# SzineszFeny.net
KiCad netlist of a schematic drawn in EAGLE
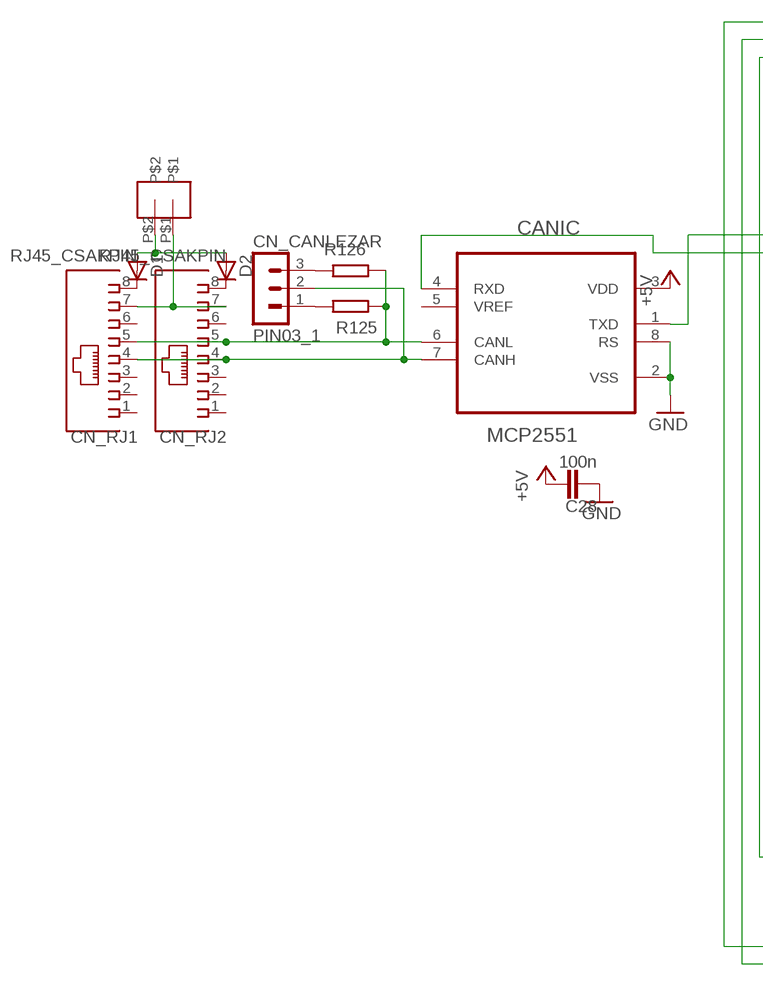
[diagram p0: schematic, sheet 1, part 1 of 2]
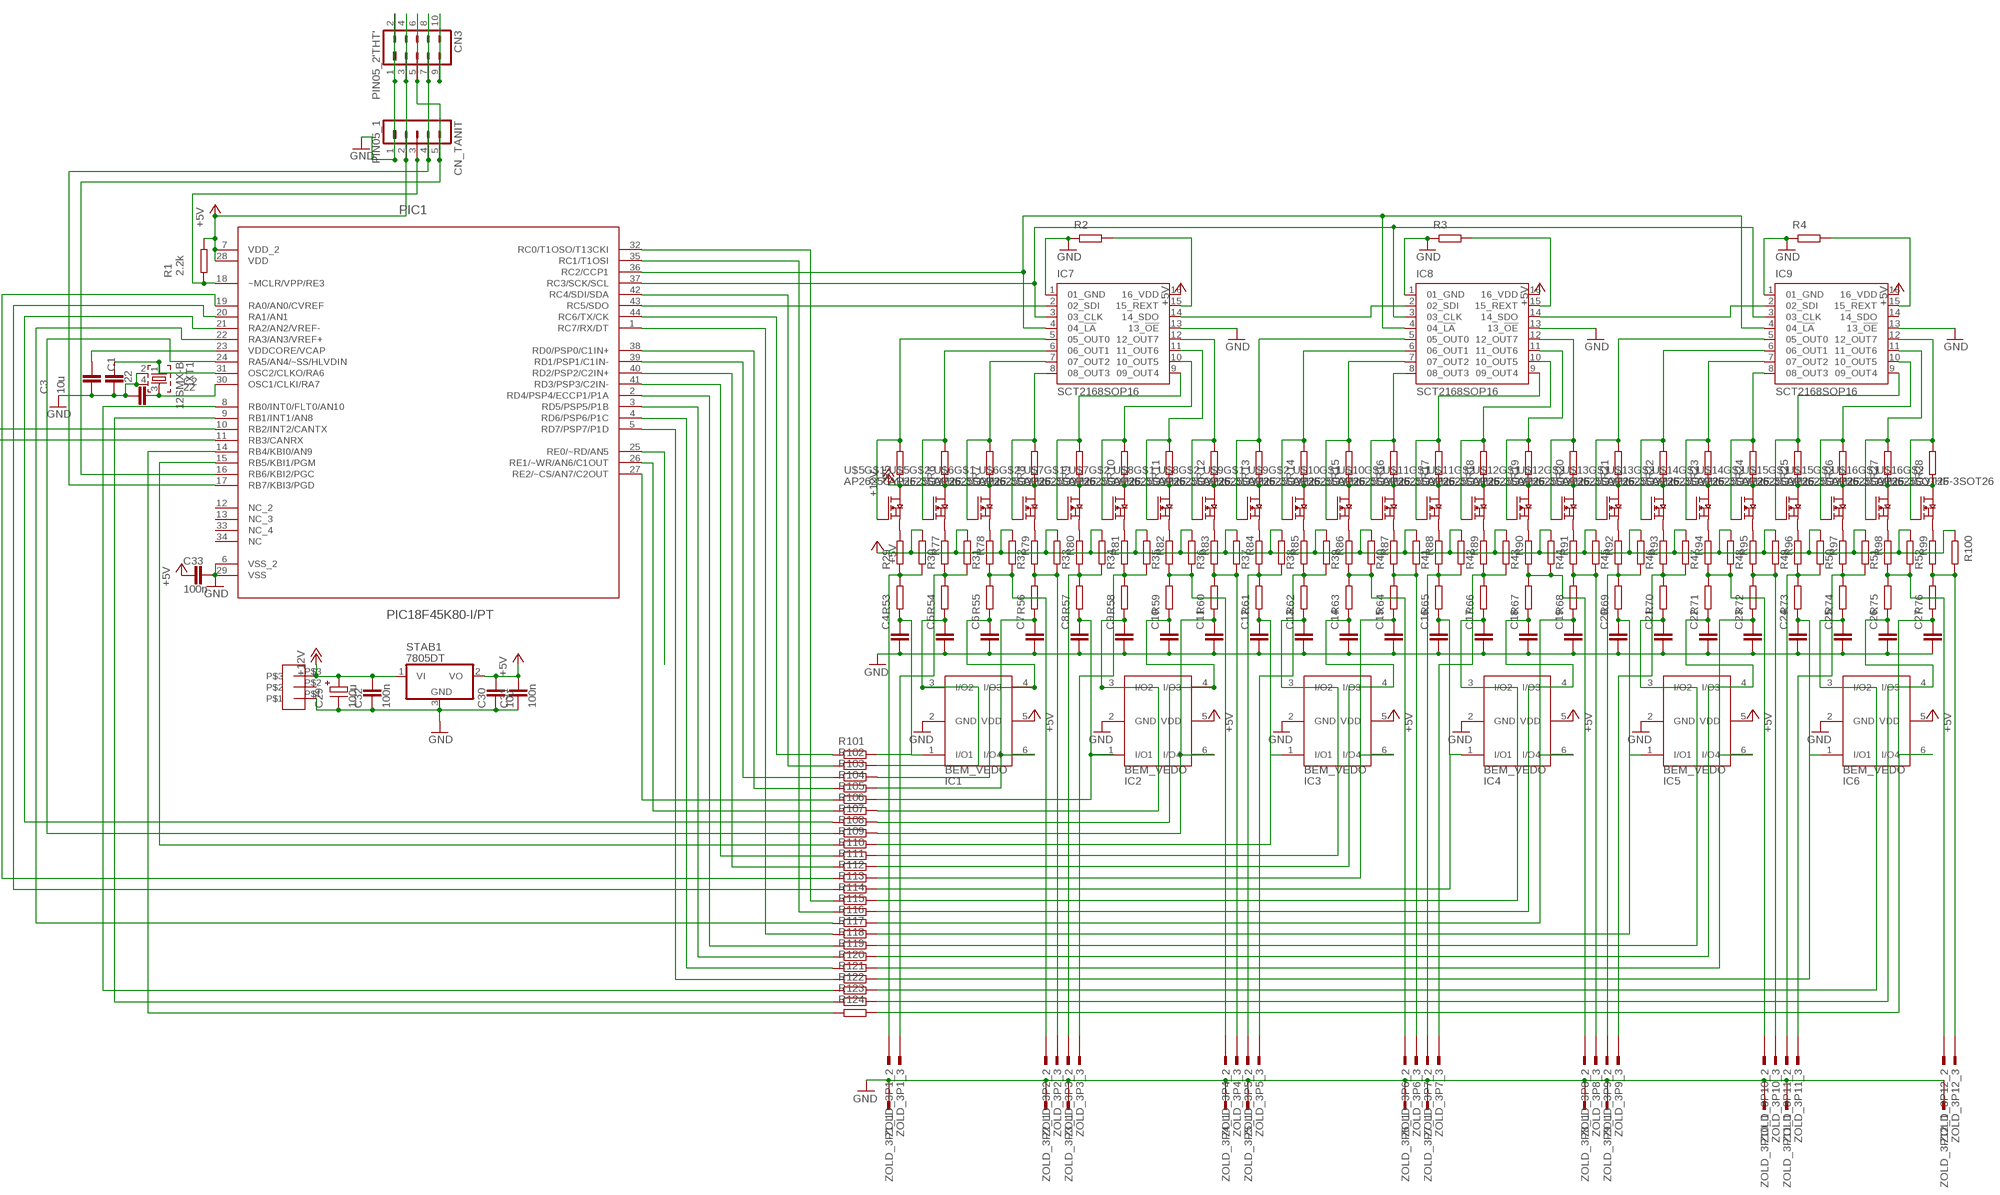
[diagram p1: schematic, sheet 1, part 2 of 2]

(export (version "E")
  (design (tool "Eeschema 10.0.6"))
  (components
    (comp (ref "C1")
      (value "22")
      (footprint "eagle-import:R0805")
      (libsource (lib "eagle-import") (part "C0805"))
    )
    (comp (ref "C2")
      (value "22")
      (footprint "eagle-import:R0805")
      (libsource (lib "eagle-import") (part "C0805"))
    )
    (comp (ref "C3")
      (value "10u")
      (footprint "eagle-import:R0805")
      (libsource (lib "eagle-import") (part "C0805"))
    )
    (comp (ref "C4")
      (value "C0805")
      (footprint "eagle-import:R0805")
      (libsource (lib "eagle-import") (part "C0805"))
    )
    (comp (ref "C5")
      (value "C0805")
      (footprint "eagle-import:R0805")
      (libsource (lib "eagle-import") (part "C0805"))
    )
    (comp (ref "C6")
      (value "C0805")
      (footprint "eagle-import:R0805")
      (libsource (lib "eagle-import") (part "C0805"))
    )
    (comp (ref "C7")
      (value "C0805")
      (footprint "eagle-import:R0805")
      (libsource (lib "eagle-import") (part "C0805"))
    )
    (comp (ref "C8")
      (value "C0805")
      (footprint "eagle-import:R0805")
      (libsource (lib "eagle-import") (part "C0805"))
    )
    (comp (ref "C9")
      (value "C0805")
      (footprint "eagle-import:R0805")
      (libsource (lib "eagle-import") (part "C0805"))
    )
    (comp (ref "C10")
      (value "C0805")
      (footprint "eagle-import:R0805")
      (libsource (lib "eagle-import") (part "C0805"))
    )
    (comp (ref "C11")
      (value "C0805")
      (footprint "eagle-import:R0805")
      (libsource (lib "eagle-import") (part "C0805"))
    )
    (comp (ref "C12")
      (value "C0805")
      (footprint "eagle-import:R0805")
      (libsource (lib "eagle-import") (part "C0805"))
    )
    (comp (ref "C13")
      (value "C0805")
      (footprint "eagle-import:R0805")
      (libsource (lib "eagle-import") (part "C0805"))
    )
    (comp (ref "C14")
      (value "C0805")
      (footprint "eagle-import:R0805")
      (libsource (lib "eagle-import") (part "C0805"))
    )
    (comp (ref "C15")
      (value "C0805")
      (footprint "eagle-import:R0805")
      (libsource (lib "eagle-import") (part "C0805"))
    )
    (comp (ref "C16")
      (value "C0805")
      (footprint "eagle-import:R0805")
      (libsource (lib "eagle-import") (part "C0805"))
    )
    (comp (ref "C17")
      (value "C0805")
      (footprint "eagle-import:R0805")
      (libsource (lib "eagle-import") (part "C0805"))
    )
    (comp (ref "C18")
      (value "C0805")
      (footprint "eagle-import:R0805")
      (libsource (lib "eagle-import") (part "C0805"))
    )
    (comp (ref "C19")
      (value "C0805")
      (footprint "eagle-import:R0805")
      (libsource (lib "eagle-import") (part "C0805"))
    )
    (comp (ref "C20")
      (value "C0805")
      (footprint "eagle-import:R0805")
      (libsource (lib "eagle-import") (part "C0805"))
    )
    (comp (ref "C21")
      (value "C0805")
      (footprint "eagle-import:R0805")
      (libsource (lib "eagle-import") (part "C0805"))
    )
    (comp (ref "C22")
      (value "C0805")
      (footprint "eagle-import:R0805")
      (libsource (lib "eagle-import") (part "C0805"))
    )
    (comp (ref "C23")
      (value "C0805")
      (footprint "eagle-import:R0805")
      (libsource (lib "eagle-import") (part "C0805"))
    )
    (comp (ref "C24")
      (value "C0805")
      (footprint "eagle-import:R0805")
      (libsource (lib "eagle-import") (part "C0805"))
    )
    (comp (ref "C25")
      (value "C0805")
      (footprint "eagle-import:R0805")
      (libsource (lib "eagle-import") (part "C0805"))
    )
    (comp (ref "C26")
      (value "C0805")
      (footprint "eagle-import:R0805")
      (libsource (lib "eagle-import") (part "C0805"))
    )
    (comp (ref "C27")
      (value "C0805")
      (footprint "eagle-import:R0805")
      (libsource (lib "eagle-import") (part "C0805"))
    )
    (comp (ref "C28")
      (value "100n")
      (footprint "eagle-import:R0805")
      (libsource (lib "eagle-import") (part "C0805"))
    )
    (comp (ref "C29")
      (value "100u")
      (footprint "eagle-import:C_EL1RASZT07")
      (libsource (lib "eagle-import") (part "C_EL1R07"))
    )
    (comp (ref "C30")
      (value "10u")
      (footprint "eagle-import:R0805")
      (libsource (lib "eagle-import") (part "C0805"))
    )
    (comp (ref "C31")
      (value "100n")
      (footprint "eagle-import:R0805")
      (libsource (lib "eagle-import") (part "C0805"))
    )
    (comp (ref "C32")
      (value "100n")
      (footprint "eagle-import:R0805")
      (libsource (lib "eagle-import") (part "C0805"))
    )
    (comp (ref "C33")
      (value "100n")
      (footprint "eagle-import:R0805")
      (libsource (lib "eagle-import") (part "C0805"))
    )
    (comp (ref "CANIC")
      (value "MCP2551")
      (footprint "eagle-import:DIP254P762X432-8")
      (fields (field (name "MPN") "MCP2551-I/P"))
      (libsource (lib "eagle-import") (part "MCP2551-I/P"))
    )
    (comp (ref "CN3")
      (value "PIN05_2'THT'")
      (footprint "eagle-import:PIN05_2")
      (libsource (lib "eagle-import") (part "PIN05_2'THT'"))
    )
    (comp (ref "CN_CANLEZAR")
      (value "PIN03_1")
      (footprint "eagle-import:PIN03_1")
      (libsource (lib "eagle-import") (part "PIN03_1"))
    )
    (comp (ref "CN_RJ1")
      (value "RJ45_CSAKPIN")
      (footprint "eagle-import:RJ45_CSAKPIN")
      (libsource (lib "eagle-import") (part "RJ45_CSAKPIN"))
    )
    (comp (ref "CN_RJ2")
      (value "RJ45_CSAKPIN")
      (footprint "eagle-import:RJ45_CSAKPIN")
      (libsource (lib "eagle-import") (part "RJ45_CSAKPIN"))
    )
    (comp (ref "CN_TANIT")
      (value "PIN05_1")
      (footprint "eagle-import:PIN05_1")
      (libsource (lib "eagle-import") (part "PIN05_1"))
    )
    (comp (ref "D1")
      (value "DDO214AC")
      (footprint "eagle-import:DO214AC")
      (libsource (lib "eagle-import") (part "DDO214AC"))
    )
    (comp (ref "D2")
      (value "DDO214AC")
      (footprint "eagle-import:DO214AC")
      (libsource (lib "eagle-import") (part "DDO214AC"))
    )
    (comp (ref "IC1")
      (value "BEM_VEDO")
      (footprint "eagle-import:TSOP-6")
      (libsource (lib "eagle-import") (part "BEM_VEDO"))
    )
    (comp (ref "IC2")
      (value "BEM_VEDO")
      (footprint "eagle-import:TSOP-6")
      (libsource (lib "eagle-import") (part "BEM_VEDO"))
    )
    (comp (ref "IC3")
      (value "BEM_VEDO")
      (footprint "eagle-import:TSOP-6")
      (libsource (lib "eagle-import") (part "BEM_VEDO"))
    )
    (comp (ref "IC4")
      (value "BEM_VEDO")
      (footprint "eagle-import:TSOP-6")
      (libsource (lib "eagle-import") (part "BEM_VEDO"))
    )
    (comp (ref "IC5")
      (value "BEM_VEDO")
      (footprint "eagle-import:TSOP-6")
      (libsource (lib "eagle-import") (part "BEM_VEDO"))
    )
    (comp (ref "IC6")
      (value "BEM_VEDO")
      (footprint "eagle-import:TSOP-6")
      (libsource (lib "eagle-import") (part "BEM_VEDO"))
    )
    (comp (ref "IC7")
      (value "SCT2168SOP16")
      (footprint "eagle-import:SO16")
      (libsource (lib "eagle-import") (part "SCT2168SOP16"))
    )
    (comp (ref "IC8")
      (value "SCT2168SOP16")
      (footprint "eagle-import:SO16")
      (libsource (lib "eagle-import") (part "SCT2168SOP16"))
    )
    (comp (ref "IC9")
      (value "SCT2168SOP16")
      (footprint "eagle-import:SO16")
      (libsource (lib "eagle-import") (part "SCT2168SOP16"))
    )
    (comp (ref "PIC1")
      (value "PIC18F45K80-I/PT")
      (footprint "eagle-import:QFP80P1200X1200X120-44N")
      (fields (field (name "MPN") "PIC18F4580-I/PT"))
      (libsource (lib "eagle-import") (part "PIC18F45K80-I/PT"))
    )
    (comp (ref "R1")
      (value "2.2k")
      (footprint "eagle-import:R0805@1")
      (libsource (lib "eagle-import") (part "R_EU0805"))
    )
    (comp (ref "R2")
      (value "R_EU0805")
      (footprint "eagle-import:R0805@1")
      (libsource (lib "eagle-import") (part "R_EU0805"))
    )
    (comp (ref "R3")
      (value "R_EU0805")
      (footprint "eagle-import:R0805@1")
      (libsource (lib "eagle-import") (part "R_EU0805"))
    )
    (comp (ref "R4")
      (value "R_EU0805")
      (footprint "eagle-import:R0805@1")
      (libsource (lib "eagle-import") (part "R_EU0805"))
    )
    (comp (ref "R5")
      (value "R_EU0805")
      (footprint "eagle-import:R0805@1")
      (libsource (lib "eagle-import") (part "R_EU0805"))
    )
    (comp (ref "R6")
      (value "R_EU0805")
      (footprint "eagle-import:R0805@1")
      (libsource (lib "eagle-import") (part "R_EU0805"))
    )
    (comp (ref "R7")
      (value "R_EU0805")
      (footprint "eagle-import:R0805@1")
      (libsource (lib "eagle-import") (part "R_EU0805"))
    )
    (comp (ref "R8")
      (value "R_EU0805")
      (footprint "eagle-import:R0805@1")
      (libsource (lib "eagle-import") (part "R_EU0805"))
    )
    (comp (ref "R9")
      (value "R_EU0805")
      (footprint "eagle-import:R0805@1")
      (libsource (lib "eagle-import") (part "R_EU0805"))
    )
    (comp (ref "R10")
      (value "R_EU0805")
      (footprint "eagle-import:R0805@1")
      (libsource (lib "eagle-import") (part "R_EU0805"))
    )
    (comp (ref "R11")
      (value "R_EU0805")
      (footprint "eagle-import:R0805@1")
      (libsource (lib "eagle-import") (part "R_EU0805"))
    )
    (comp (ref "R12")
      (value "R_EU0805")
      (footprint "eagle-import:R0805@1")
      (libsource (lib "eagle-import") (part "R_EU0805"))
    )
    (comp (ref "R13")
      (value "R_EU0805")
      (footprint "eagle-import:R0805@1")
      (libsource (lib "eagle-import") (part "R_EU0805"))
    )
    (comp (ref "R14")
      (value "R_EU0805")
      (footprint "eagle-import:R0805@1")
      (libsource (lib "eagle-import") (part "R_EU0805"))
    )
    (comp (ref "R15")
      (value "R_EU0805")
      (footprint "eagle-import:R0805@1")
      (libsource (lib "eagle-import") (part "R_EU0805"))
    )
    (comp (ref "R16")
      (value "R_EU0805")
      (footprint "eagle-import:R0805@1")
      (libsource (lib "eagle-import") (part "R_EU0805"))
    )
    (comp (ref "R17")
      (value "R_EU0805")
      (footprint "eagle-import:R0805@1")
      (libsource (lib "eagle-import") (part "R_EU0805"))
    )
    (comp (ref "R18")
      (value "R_EU0805")
      (footprint "eagle-import:R0805@1")
      (libsource (lib "eagle-import") (part "R_EU0805"))
    )
    (comp (ref "R19")
      (value "R_EU0805")
      (footprint "eagle-import:R0805@1")
      (libsource (lib "eagle-import") (part "R_EU0805"))
    )
    (comp (ref "R20")
      (value "R_EU0805")
      (footprint "eagle-import:R0805@1")
      (libsource (lib "eagle-import") (part "R_EU0805"))
    )
    (comp (ref "R21")
      (value "R_EU0805")
      (footprint "eagle-import:R0805@1")
      (libsource (lib "eagle-import") (part "R_EU0805"))
    )
    (comp (ref "R22")
      (value "R_EU0805")
      (footprint "eagle-import:R0805@1")
      (libsource (lib "eagle-import") (part "R_EU0805"))
    )
    (comp (ref "R23")
      (value "R_EU0805")
      (footprint "eagle-import:R0805@1")
      (libsource (lib "eagle-import") (part "R_EU0805"))
    )
    (comp (ref "R24")
      (value "R_EU0805")
      (footprint "eagle-import:R0805@1")
      (libsource (lib "eagle-import") (part "R_EU0805"))
    )
    (comp (ref "R25")
      (value "R_EU0805")
      (footprint "eagle-import:R0805@1")
      (libsource (lib "eagle-import") (part "R_EU0805"))
    )
    (comp (ref "R26")
      (value "R_EU0805")
      (footprint "eagle-import:R0805@1")
      (libsource (lib "eagle-import") (part "R_EU0805"))
    )
    (comp (ref "R27")
      (value "R_EU0805")
      (footprint "eagle-import:R0805@1")
      (libsource (lib "eagle-import") (part "R_EU0805"))
    )
    (comp (ref "R28")
      (value "R_EU0805")
      (footprint "eagle-import:R0805@1")
      (libsource (lib "eagle-import") (part "R_EU0805"))
    )
    (comp (ref "R29")
      (value "R_EU0805")
      (footprint "eagle-import:R0805@1")
      (libsource (lib "eagle-import") (part "R_EU0805"))
    )
    (comp (ref "R30")
      (value "R_EU0805")
      (footprint "eagle-import:R0805@1")
      (libsource (lib "eagle-import") (part "R_EU0805"))
    )
    (comp (ref "R31")
      (value "R_EU0805")
      (footprint "eagle-import:R0805@1")
      (libsource (lib "eagle-import") (part "R_EU0805"))
    )
    (comp (ref "R32")
      (value "R_EU0805")
      (footprint "eagle-import:R0805@1")
      (libsource (lib "eagle-import") (part "R_EU0805"))
    )
    (comp (ref "R33")
      (value "R_EU0805")
      (footprint "eagle-import:R0805@1")
      (libsource (lib "eagle-import") (part "R_EU0805"))
    )
    (comp (ref "R34")
      (value "R_EU0805")
      (footprint "eagle-import:R0805@1")
      (libsource (lib "eagle-import") (part "R_EU0805"))
    )
    (comp (ref "R35")
      (value "R_EU0805")
      (footprint "eagle-import:R0805@1")
      (libsource (lib "eagle-import") (part "R_EU0805"))
    )
    (comp (ref "R36")
      (value "R_EU0805")
      (footprint "eagle-import:R0805@1")
      (libsource (lib "eagle-import") (part "R_EU0805"))
    )
    (comp (ref "R37")
      (value "R_EU0805")
      (footprint "eagle-import:R0805@1")
      (libsource (lib "eagle-import") (part "R_EU0805"))
    )
    (comp (ref "R38")
      (value "R_EU0805")
      (footprint "eagle-import:R0805@1")
      (libsource (lib "eagle-import") (part "R_EU0805"))
    )
    (comp (ref "R39")
      (value "R_EU0805")
      (footprint "eagle-import:R0805@1")
      (libsource (lib "eagle-import") (part "R_EU0805"))
    )
    (comp (ref "R40")
      (value "R_EU0805")
      (footprint "eagle-import:R0805@1")
      (libsource (lib "eagle-import") (part "R_EU0805"))
    )
    (comp (ref "R41")
      (value "R_EU0805")
      (footprint "eagle-import:R0805@1")
      (libsource (lib "eagle-import") (part "R_EU0805"))
    )
    (comp (ref "R42")
      (value "R_EU0805")
      (footprint "eagle-import:R0805@1")
      (libsource (lib "eagle-import") (part "R_EU0805"))
    )
    (comp (ref "R43")
      (value "R_EU0805")
      (footprint "eagle-import:R0805@1")
      (libsource (lib "eagle-import") (part "R_EU0805"))
    )
    (comp (ref "R44")
      (value "R_EU0805")
      (footprint "eagle-import:R0805@1")
      (libsource (lib "eagle-import") (part "R_EU0805"))
    )
    (comp (ref "R45")
      (value "R_EU0805")
      (footprint "eagle-import:R0805@1")
      (libsource (lib "eagle-import") (part "R_EU0805"))
    )
    (comp (ref "R46")
      (value "R_EU0805")
      (footprint "eagle-import:R0805@1")
      (libsource (lib "eagle-import") (part "R_EU0805"))
    )
    (comp (ref "R47")
      (value "R_EU0805")
      (footprint "eagle-import:R0805@1")
      (libsource (lib "eagle-import") (part "R_EU0805"))
    )
    (comp (ref "R48")
      (value "R_EU0805")
      (footprint "eagle-import:R0805@1")
      (libsource (lib "eagle-import") (part "R_EU0805"))
    )
    (comp (ref "R49")
      (value "R_EU0805")
      (footprint "eagle-import:R0805@1")
      (libsource (lib "eagle-import") (part "R_EU0805"))
    )
    (comp (ref "R50")
      (value "R_EU0805")
      (footprint "eagle-import:R0805@1")
      (libsource (lib "eagle-import") (part "R_EU0805"))
    )
    (comp (ref "R51")
      (value "R_EU0805")
      (footprint "eagle-import:R0805@1")
      (libsource (lib "eagle-import") (part "R_EU0805"))
    )
    (comp (ref "R52")
      (value "R_EU0805")
      (footprint "eagle-import:R0805@1")
      (libsource (lib "eagle-import") (part "R_EU0805"))
    )
    (comp (ref "R53")
      (value "R_EU0805")
      (footprint "eagle-import:R0805@1")
      (libsource (lib "eagle-import") (part "R_EU0805"))
    )
    (comp (ref "R54")
      (value "R_EU0805")
      (footprint "eagle-import:R0805@1")
      (libsource (lib "eagle-import") (part "R_EU0805"))
    )
    (comp (ref "R55")
      (value "R_EU0805")
      (footprint "eagle-import:R0805@1")
      (libsource (lib "eagle-import") (part "R_EU0805"))
    )
    (comp (ref "R56")
      (value "R_EU0805")
      (footprint "eagle-import:R0805@1")
      (libsource (lib "eagle-import") (part "R_EU0805"))
    )
    (comp (ref "R57")
      (value "R_EU0805")
      (footprint "eagle-import:R0805@1")
      (libsource (lib "eagle-import") (part "R_EU0805"))
    )
    (comp (ref "R58")
      (value "R_EU0805")
      (footprint "eagle-import:R0805@1")
      (libsource (lib "eagle-import") (part "R_EU0805"))
    )
    (comp (ref "R59")
      (value "R_EU0805")
      (footprint "eagle-import:R0805@1")
      (libsource (lib "eagle-import") (part "R_EU0805"))
    )
    (comp (ref "R60")
      (value "R_EU0805")
      (footprint "eagle-import:R0805@1")
      (libsource (lib "eagle-import") (part "R_EU0805"))
    )
    (comp (ref "R61")
      (value "R_EU0805")
      (footprint "eagle-import:R0805@1")
      (libsource (lib "eagle-import") (part "R_EU0805"))
    )
    (comp (ref "R62")
      (value "R_EU0805")
      (footprint "eagle-import:R0805@1")
      (libsource (lib "eagle-import") (part "R_EU0805"))
    )
    (comp (ref "R63")
      (value "R_EU0805")
      (footprint "eagle-import:R0805@1")
      (libsource (lib "eagle-import") (part "R_EU0805"))
    )
    (comp (ref "R64")
      (value "R_EU0805")
      (footprint "eagle-import:R0805@1")
      (libsource (lib "eagle-import") (part "R_EU0805"))
    )
    (comp (ref "R65")
      (value "R_EU0805")
      (footprint "eagle-import:R0805@1")
      (libsource (lib "eagle-import") (part "R_EU0805"))
    )
    (comp (ref "R66")
      (value "R_EU0805")
      (footprint "eagle-import:R0805@1")
      (libsource (lib "eagle-import") (part "R_EU0805"))
    )
    (comp (ref "R67")
      (value "R_EU0805")
      (footprint "eagle-import:R0805@1")
      (libsource (lib "eagle-import") (part "R_EU0805"))
    )
    (comp (ref "R68")
      (value "R_EU0805")
      (footprint "eagle-import:R0805@1")
      (libsource (lib "eagle-import") (part "R_EU0805"))
    )
    (comp (ref "R69")
      (value "R_EU0805")
      (footprint "eagle-import:R0805@1")
      (libsource (lib "eagle-import") (part "R_EU0805"))
    )
    (comp (ref "R70")
      (value "R_EU0805")
      (footprint "eagle-import:R0805@1")
      (libsource (lib "eagle-import") (part "R_EU0805"))
    )
    (comp (ref "R71")
      (value "R_EU0805")
      (footprint "eagle-import:R0805@1")
      (libsource (lib "eagle-import") (part "R_EU0805"))
    )
    (comp (ref "R72")
      (value "R_EU0805")
      (footprint "eagle-import:R0805@1")
      (libsource (lib "eagle-import") (part "R_EU0805"))
    )
    (comp (ref "R73")
      (value "R_EU0805")
      (footprint "eagle-import:R0805@1")
      (libsource (lib "eagle-import") (part "R_EU0805"))
    )
    (comp (ref "R74")
      (value "R_EU0805")
      (footprint "eagle-import:R0805@1")
      (libsource (lib "eagle-import") (part "R_EU0805"))
    )
    (comp (ref "R75")
      (value "R_EU0805")
      (footprint "eagle-import:R0805@1")
      (libsource (lib "eagle-import") (part "R_EU0805"))
    )
    (comp (ref "R76")
      (value "R_EU0805")
      (footprint "eagle-import:R0805@1")
      (libsource (lib "eagle-import") (part "R_EU0805"))
    )
    (comp (ref "R77")
      (value "R_EU0805")
      (footprint "eagle-import:R0805@1")
      (libsource (lib "eagle-import") (part "R_EU0805"))
    )
    (comp (ref "R78")
      (value "R_EU0805")
      (footprint "eagle-import:R0805@1")
      (libsource (lib "eagle-import") (part "R_EU0805"))
    )
    (comp (ref "R79")
      (value "R_EU0805")
      (footprint "eagle-import:R0805@1")
      (libsource (lib "eagle-import") (part "R_EU0805"))
    )
    (comp (ref "R80")
      (value "R_EU0805")
      (footprint "eagle-import:R0805@1")
      (libsource (lib "eagle-import") (part "R_EU0805"))
    )
    (comp (ref "R81")
      (value "R_EU0805")
      (footprint "eagle-import:R0805@1")
      (libsource (lib "eagle-import") (part "R_EU0805"))
    )
    (comp (ref "R82")
      (value "R_EU0805")
      (footprint "eagle-import:R0805@1")
      (libsource (lib "eagle-import") (part "R_EU0805"))
    )
    (comp (ref "R83")
      (value "R_EU0805")
      (footprint "eagle-import:R0805@1")
      (libsource (lib "eagle-import") (part "R_EU0805"))
    )
    (comp (ref "R84")
      (value "R_EU0805")
      (footprint "eagle-import:R0805@1")
      (libsource (lib "eagle-import") (part "R_EU0805"))
    )
    (comp (ref "R85")
      (value "R_EU0805")
      (footprint "eagle-import:R0805@1")
      (libsource (lib "eagle-import") (part "R_EU0805"))
    )
    (comp (ref "R86")
      (value "R_EU0805")
      (footprint "eagle-import:R0805@1")
      (libsource (lib "eagle-import") (part "R_EU0805"))
    )
    (comp (ref "R87")
      (value "R_EU0805")
      (footprint "eagle-import:R0805@1")
      (libsource (lib "eagle-import") (part "R_EU0805"))
    )
    (comp (ref "R88")
      (value "R_EU0805")
      (footprint "eagle-import:R0805@1")
      (libsource (lib "eagle-import") (part "R_EU0805"))
    )
    (comp (ref "R89")
      (value "R_EU0805")
      (footprint "eagle-import:R0805@1")
      (libsource (lib "eagle-import") (part "R_EU0805"))
    )
    (comp (ref "R90")
      (value "R_EU0805")
      (footprint "eagle-import:R0805@1")
      (libsource (lib "eagle-import") (part "R_EU0805"))
    )
    (comp (ref "R91")
      (value "R_EU0805")
      (footprint "eagle-import:R0805@1")
      (libsource (lib "eagle-import") (part "R_EU0805"))
    )
    (comp (ref "R92")
      (value "R_EU0805")
      (footprint "eagle-import:R0805@1")
      (libsource (lib "eagle-import") (part "R_EU0805"))
    )
    (comp (ref "R93")
      (value "R_EU0805")
      (footprint "eagle-import:R0805@1")
      (libsource (lib "eagle-import") (part "R_EU0805"))
    )
    (comp (ref "R94")
      (value "R_EU0805")
      (footprint "eagle-import:R0805@1")
      (libsource (lib "eagle-import") (part "R_EU0805"))
    )
    (comp (ref "R95")
      (value "R_EU0805")
      (footprint "eagle-import:R0805@1")
      (libsource (lib "eagle-import") (part "R_EU0805"))
    )
    (comp (ref "R96")
      (value "R_EU0805")
      (footprint "eagle-import:R0805@1")
      (libsource (lib "eagle-import") (part "R_EU0805"))
    )
    (comp (ref "R97")
      (value "R_EU0805")
      (footprint "eagle-import:R0805@1")
      (libsource (lib "eagle-import") (part "R_EU0805"))
    )
    (comp (ref "R98")
      (value "R_EU0805")
      (footprint "eagle-import:R0805@1")
      (libsource (lib "eagle-import") (part "R_EU0805"))
    )
    (comp (ref "R99")
      (value "R_EU0805")
      (footprint "eagle-import:R0805@1")
      (libsource (lib "eagle-import") (part "R_EU0805"))
    )
    (comp (ref "R100")
      (value "R_EU0805")
      (footprint "eagle-import:R0805@1")
      (libsource (lib "eagle-import") (part "R_EU0805"))
    )
    (comp (ref "R101")
      (value "R_EU0805")
      (footprint "eagle-import:R0805@1")
      (libsource (lib "eagle-import") (part "R_EU0805"))
    )
    (comp (ref "R102")
      (value "R_EU0805")
      (footprint "eagle-import:R0805@1")
      (libsource (lib "eagle-import") (part "R_EU0805"))
    )
    (comp (ref "R103")
      (value "R_EU0805")
      (footprint "eagle-import:R0805@1")
      (libsource (lib "eagle-import") (part "R_EU0805"))
    )
    (comp (ref "R104")
      (value "R_EU0805")
      (footprint "eagle-import:R0805@1")
      (libsource (lib "eagle-import") (part "R_EU0805"))
    )
    (comp (ref "R105")
      (value "R_EU0805")
      (footprint "eagle-import:R0805@1")
      (libsource (lib "eagle-import") (part "R_EU0805"))
    )
    (comp (ref "R106")
      (value "R_EU0805")
      (footprint "eagle-import:R0805@1")
      (libsource (lib "eagle-import") (part "R_EU0805"))
    )
    (comp (ref "R107")
      (value "R_EU0805")
      (footprint "eagle-import:R0805@1")
      (libsource (lib "eagle-import") (part "R_EU0805"))
    )
    (comp (ref "R108")
      (value "R_EU0805")
      (footprint "eagle-import:R0805@1")
      (libsource (lib "eagle-import") (part "R_EU0805"))
    )
    (comp (ref "R109")
      (value "R_EU0805")
      (footprint "eagle-import:R0805@1")
      (libsource (lib "eagle-import") (part "R_EU0805"))
    )
    (comp (ref "R110")
      (value "R_EU0805")
      (footprint "eagle-import:R0805@1")
      (libsource (lib "eagle-import") (part "R_EU0805"))
    )
    (comp (ref "R111")
      (value "R_EU0805")
      (footprint "eagle-import:R0805@1")
      (libsource (lib "eagle-import") (part "R_EU0805"))
    )
    (comp (ref "R112")
      (value "R_EU0805")
      (footprint "eagle-import:R0805@1")
      (libsource (lib "eagle-import") (part "R_EU0805"))
    )
    (comp (ref "R113")
      (value "R_EU0805")
      (footprint "eagle-import:R0805@1")
      (libsource (lib "eagle-import") (part "R_EU0805"))
    )
    (comp (ref "R114")
      (value "R_EU0805")
      (footprint "eagle-import:R0805@1")
      (libsource (lib "eagle-import") (part "R_EU0805"))
    )
    (comp (ref "R115")
      (value "R_EU0805")
      (footprint "eagle-import:R0805@1")
      (libsource (lib "eagle-import") (part "R_EU0805"))
    )
    (comp (ref "R116")
      (value "R_EU0805")
      (footprint "eagle-import:R0805@1")
      (libsource (lib "eagle-import") (part "R_EU0805"))
    )
    (comp (ref "R117")
      (value "R_EU0805")
      (footprint "eagle-import:R0805@1")
      (libsource (lib "eagle-import") (part "R_EU0805"))
    )
    (comp (ref "R118")
      (value "R_EU0805")
      (footprint "eagle-import:R0805@1")
      (libsource (lib "eagle-import") (part "R_EU0805"))
    )
    (comp (ref "R119")
      (value "R_EU0805")
      (footprint "eagle-import:R0805@1")
      (libsource (lib "eagle-import") (part "R_EU0805"))
    )
    (comp (ref "R120")
      (value "R_EU0805")
      (footprint "eagle-import:R0805@1")
      (libsource (lib "eagle-import") (part "R_EU0805"))
    )
    (comp (ref "R121")
      (value "R_EU0805")
      (footprint "eagle-import:R0805@1")
      (libsource (lib "eagle-import") (part "R_EU0805"))
    )
    (comp (ref "R122")
      (value "R_EU0805")
      (footprint "eagle-import:R0805@1")
      (libsource (lib "eagle-import") (part "R_EU0805"))
    )
    (comp (ref "R123")
      (value "R_EU0805")
      (footprint "eagle-import:R0805@1")
      (libsource (lib "eagle-import") (part "R_EU0805"))
    )
    (comp (ref "R124")
      (value "R_EU0805")
      (footprint "eagle-import:R0805@1")
      (libsource (lib "eagle-import") (part "R_EU0805"))
    )
    (comp (ref "R125")
      (value "R_EU0805")
      (footprint "eagle-import:R0805@1")
      (libsource (lib "eagle-import") (part "R_EU0805"))
    )
    (comp (ref "R126")
      (value "R_EU0805")
      (footprint "eagle-import:R0805@1")
      (libsource (lib "eagle-import") (part "R_EU0805"))
    )
    (comp (ref "STAB1")
      (value "7805DT")
      (footprint "eagle-import:TO252")
      (libsource (lib "eagle-import") (part "78DT05"))
    )
    (comp (ref "U$5")
      (value "AP2625GY-HF-3SOT26")
      (footprint "eagle-import:SOT26")
      (libsource (lib "eagle-import") (part "AP2625GY-HF-3SOT26"))
    )
    (comp (ref "U$6")
      (value "AP2625GY-HF-3SOT26")
      (footprint "eagle-import:SOT26")
      (libsource (lib "eagle-import") (part "AP2625GY-HF-3SOT26"))
    )
    (comp (ref "U$7")
      (value "AP2625GY-HF-3SOT26")
      (footprint "eagle-import:SOT26")
      (libsource (lib "eagle-import") (part "AP2625GY-HF-3SOT26"))
    )
    (comp (ref "U$8")
      (value "AP2625GY-HF-3SOT26")
      (footprint "eagle-import:SOT26")
      (libsource (lib "eagle-import") (part "AP2625GY-HF-3SOT26"))
    )
    (comp (ref "U$9")
      (value "AP2625GY-HF-3SOT26")
      (footprint "eagle-import:SOT26")
      (libsource (lib "eagle-import") (part "AP2625GY-HF-3SOT26"))
    )
    (comp (ref "U$10")
      (value "AP2625GY-HF-3SOT26")
      (footprint "eagle-import:SOT26")
      (libsource (lib "eagle-import") (part "AP2625GY-HF-3SOT26"))
    )
    (comp (ref "U$11")
      (value "AP2625GY-HF-3SOT26")
      (footprint "eagle-import:SOT26")
      (libsource (lib "eagle-import") (part "AP2625GY-HF-3SOT26"))
    )
    (comp (ref "U$12")
      (value "AP2625GY-HF-3SOT26")
      (footprint "eagle-import:SOT26")
      (libsource (lib "eagle-import") (part "AP2625GY-HF-3SOT26"))
    )
    (comp (ref "U$13")
      (value "AP2625GY-HF-3SOT26")
      (footprint "eagle-import:SOT26")
      (libsource (lib "eagle-import") (part "AP2625GY-HF-3SOT26"))
    )
    (comp (ref "U$14")
      (value "AP2625GY-HF-3SOT26")
      (footprint "eagle-import:SOT26")
      (libsource (lib "eagle-import") (part "AP2625GY-HF-3SOT26"))
    )
    (comp (ref "U$15")
      (value "AP2625GY-HF-3SOT26")
      (footprint "eagle-import:SOT26")
      (libsource (lib "eagle-import") (part "AP2625GY-HF-3SOT26"))
    )
    (comp (ref "U$16")
      (value "AP2625GY-HF-3SOT26")
      (footprint "eagle-import:SOT26")
      (libsource (lib "eagle-import") (part "AP2625GY-HF-3SOT26"))
    )
    (comp (ref "U$20")
      (value "FEHER_TUS_3")
      (footprint "eagle-import:FEHER_TUS_3")
      (libsource (lib "eagle-import") (part "FEHER_TUS_3"))
    )
    (comp (ref "U$21")
      (value "FEHER_TUS_2ALLO")
      (footprint "eagle-import:FEHER_TUS_2")
      (libsource (lib "eagle-import") (part "FEHER_TUS_2ALLO"))
    )
    (comp (ref "XT1")
      (value "12SMX-B")
      (footprint "eagle-import:12SMX-B")
      (libsource (lib "eagle-import") (part "12SMX-B"))
    )
    (comp (ref "ZOLD_3P1")
      (value "ZOLD_KICSI_3P")
      (footprint "eagle-import:ZOLD_KICSI_3P")
      (libsource (lib "eagle-import") (part "ZOLD_KICSI_3P"))
    )
    (comp (ref "ZOLD_3P2")
      (value "ZOLD_KICSI_3P")
      (footprint "eagle-import:ZOLD_KICSI_3P")
      (libsource (lib "eagle-import") (part "ZOLD_KICSI_3P"))
    )
    (comp (ref "ZOLD_3P3")
      (value "ZOLD_KICSI_3P")
      (footprint "eagle-import:ZOLD_KICSI_3P")
      (libsource (lib "eagle-import") (part "ZOLD_KICSI_3P"))
    )
    (comp (ref "ZOLD_3P4")
      (value "ZOLD_KICSI_3P")
      (footprint "eagle-import:ZOLD_KICSI_3P")
      (libsource (lib "eagle-import") (part "ZOLD_KICSI_3P"))
    )
    (comp (ref "ZOLD_3P5")
      (value "ZOLD_KICSI_3P")
      (footprint "eagle-import:ZOLD_KICSI_3P")
      (libsource (lib "eagle-import") (part "ZOLD_KICSI_3P"))
    )
    (comp (ref "ZOLD_3P6")
      (value "ZOLD_KICSI_3P")
      (footprint "eagle-import:ZOLD_KICSI_3P")
      (libsource (lib "eagle-import") (part "ZOLD_KICSI_3P"))
    )
    (comp (ref "ZOLD_3P7")
      (value "ZOLD_KICSI_3P")
      (footprint "eagle-import:ZOLD_KICSI_3P")
      (libsource (lib "eagle-import") (part "ZOLD_KICSI_3P"))
    )
    (comp (ref "ZOLD_3P8")
      (value "ZOLD_KICSI_3P")
      (footprint "eagle-import:ZOLD_KICSI_3P")
      (libsource (lib "eagle-import") (part "ZOLD_KICSI_3P"))
    )
    (comp (ref "ZOLD_3P9")
      (value "ZOLD_KICSI_3P")
      (footprint "eagle-import:ZOLD_KICSI_3P")
      (libsource (lib "eagle-import") (part "ZOLD_KICSI_3P"))
    )
    (comp (ref "ZOLD_3P10")
      (value "ZOLD_KICSI_3P")
      (footprint "eagle-import:ZOLD_KICSI_3P")
      (libsource (lib "eagle-import") (part "ZOLD_KICSI_3P"))
    )
    (comp (ref "ZOLD_3P11")
      (value "ZOLD_KICSI_3P")
      (footprint "eagle-import:ZOLD_KICSI_3P")
      (libsource (lib "eagle-import") (part "ZOLD_KICSI_3P"))
    )
    (comp (ref "ZOLD_3P12")
      (value "ZOLD_KICSI_3P")
      (footprint "eagle-import:ZOLD_KICSI_3P")
      (libsource (lib "eagle-import") (part "ZOLD_KICSI_3P"))
    )
  )
  (nets
    (net (code "1") (name "+5V") (class "Default")
      (node (ref "C28") (pin "1") (pinfunction "1_1") (pintype "passive"))
      (node (ref "C30") (pin "1") (pinfunction "1_1") (pintype "passive"))
      (node (ref "C31") (pin "1") (pinfunction "1_1") (pintype "passive"))
      (node (ref "C33") (pin "2") (pinfunction "2_2") (pintype "passive"))
      (node (ref "CANIC") (pin "3") (pinfunction "VDD_3") (pintype "power_in"))
      (node (ref "CN3") (pin "3") (pinfunction "3_3") (pintype "passive"))
      (node (ref "CN3") (pin "4") (pinfunction "4_4") (pintype "passive"))
      (node (ref "CN_TANIT") (pin "2") (pinfunction "2_2") (pintype "passive"))
      (node (ref "IC1") (pin "5") (pinfunction "VDD_5") (pintype "bidirectional"))
      (node (ref "IC2") (pin "5") (pinfunction "VDD_5") (pintype "bidirectional"))
      (node (ref "IC3") (pin "5") (pinfunction "VDD_5") (pintype "bidirectional"))
      (node (ref "IC4") (pin "5") (pinfunction "VDD_5") (pintype "bidirectional"))
      (node (ref "IC5") (pin "5") (pinfunction "VDD_5") (pintype "bidirectional"))
      (node (ref "IC6") (pin "5") (pinfunction "VDD_5") (pintype "bidirectional"))
      (node (ref "IC7") (pin "16") (pinfunction "16_VDD_16") (pintype "power_in"))
      (node (ref "IC8") (pin "16") (pinfunction "16_VDD_16") (pintype "power_in"))
      (node (ref "IC9") (pin "16") (pinfunction "16_VDD_16") (pintype "power_in"))
      (node (ref "PIC1") (pin "28") (pinfunction "VDD_28") (pintype "power_in"))
      (node (ref "PIC1") (pin "7") (pinfunction "VDD_2_7") (pintype "power_in"))
      (node (ref "R1") (pin "2") (pinfunction "E_2") (pintype "passive"))
      (node (ref "R100") (pin "1") (pinfunction "A_1") (pintype "passive"))
      (node (ref "R77") (pin "1") (pinfunction "A_1") (pintype "passive"))
      (node (ref "R78") (pin "1") (pinfunction "A_1") (pintype "passive"))
      (node (ref "R79") (pin "1") (pinfunction "A_1") (pintype "passive"))
      (node (ref "R80") (pin "1") (pinfunction "A_1") (pintype "passive"))
      (node (ref "R81") (pin "1") (pinfunction "A_1") (pintype "passive"))
      (node (ref "R82") (pin "1") (pinfunction "A_1") (pintype "passive"))
      (node (ref "R83") (pin "1") (pinfunction "A_1") (pintype "passive"))
      (node (ref "R84") (pin "1") (pinfunction "A_1") (pintype "passive"))
      (node (ref "R85") (pin "1") (pinfunction "A_1") (pintype "passive"))
      (node (ref "R86") (pin "1") (pinfunction "A_1") (pintype "passive"))
      (node (ref "R87") (pin "1") (pinfunction "A_1") (pintype "passive"))
      (node (ref "R88") (pin "1") (pinfunction "A_1") (pintype "passive"))
      (node (ref "R89") (pin "1") (pinfunction "A_1") (pintype "passive"))
      (node (ref "R90") (pin "1") (pinfunction "A_1") (pintype "passive"))
      (node (ref "R91") (pin "1") (pinfunction "A_1") (pintype "passive"))
      (node (ref "R92") (pin "1") (pinfunction "A_1") (pintype "passive"))
      (node (ref "R93") (pin "1") (pinfunction "A_1") (pintype "passive"))
      (node (ref "R94") (pin "1") (pinfunction "A_1") (pintype "passive"))
      (node (ref "R95") (pin "1") (pinfunction "A_1") (pintype "passive"))
      (node (ref "R96") (pin "1") (pinfunction "A_1") (pintype "passive"))
      (node (ref "R97") (pin "1") (pinfunction "A_1") (pintype "passive"))
      (node (ref "R98") (pin "1") (pinfunction "A_1") (pintype "passive"))
      (node (ref "R99") (pin "1") (pinfunction "A_1") (pintype "passive"))
      (node (ref "STAB1") (pin "2") (pinfunction "VO_2") (pintype "passive"))
    )
    (net (code "2") (name "+12V") (class "Default")
      (node (ref "C29") (pin "P+") (pinfunction "P+_P+") (pintype "passive"))
      (node (ref "C32") (pin "1") (pinfunction "1_1") (pintype "passive"))
      (node (ref "R10") (pin "1") (pinfunction "A_1") (pintype "passive"))
      (node (ref "R11") (pin "1") (pinfunction "A_1") (pintype "passive"))
      (node (ref "R12") (pin "1") (pinfunction "A_1") (pintype "passive"))
      (node (ref "R13") (pin "1") (pinfunction "A_1") (pintype "passive"))
      (node (ref "R14") (pin "1") (pinfunction "A_1") (pintype "passive"))
      (node (ref "R15") (pin "1") (pinfunction "A_1") (pintype "passive"))
      (node (ref "R16") (pin "1") (pinfunction "A_1") (pintype "passive"))
      (node (ref "R17") (pin "1") (pinfunction "A_1") (pintype "passive"))
      (node (ref "R18") (pin "1") (pinfunction "A_1") (pintype "passive"))
      (node (ref "R19") (pin "1") (pinfunction "A_1") (pintype "passive"))
      (node (ref "R20") (pin "1") (pinfunction "A_1") (pintype "passive"))
      (node (ref "R21") (pin "1") (pinfunction "A_1") (pintype "passive"))
      (node (ref "R22") (pin "1") (pinfunction "A_1") (pintype "passive"))
      (node (ref "R23") (pin "1") (pinfunction "A_1") (pintype "passive"))
      (node (ref "R24") (pin "1") (pinfunction "A_1") (pintype "passive"))
      (node (ref "R25") (pin "1") (pinfunction "A_1") (pintype "passive"))
      (node (ref "R26") (pin "1") (pinfunction "A_1") (pintype "passive"))
      (node (ref "R27") (pin "1") (pinfunction "A_1") (pintype "passive"))
      (node (ref "R28") (pin "1") (pinfunction "A_1") (pintype "passive"))
      (node (ref "R5") (pin "1") (pinfunction "A_1") (pintype "passive"))
      (node (ref "R6") (pin "1") (pinfunction "A_1") (pintype "passive"))
      (node (ref "R7") (pin "1") (pinfunction "A_1") (pintype "passive"))
      (node (ref "R8") (pin "1") (pinfunction "A_1") (pintype "passive"))
      (node (ref "R9") (pin "1") (pinfunction "A_1") (pintype "passive"))
      (node (ref "STAB1") (pin "1") (pinfunction "VI_1") (pintype "input"))
      (node (ref "U$10") (pin "P$4") (pinfunction "D_P$4") (pintype "passive"))
      (node (ref "U$10") (pin "P$6") (pinfunction "D_P$6") (pintype "passive"))
      (node (ref "U$11") (pin "P$4") (pinfunction "D_P$4") (pintype "passive"))
      (node (ref "U$11") (pin "P$6") (pinfunction "D_P$6") (pintype "passive"))
      (node (ref "U$12") (pin "P$4") (pinfunction "D_P$4") (pintype "passive"))
      (node (ref "U$12") (pin "P$6") (pinfunction "D_P$6") (pintype "passive"))
      (node (ref "U$13") (pin "P$4") (pinfunction "D_P$4") (pintype "passive"))
      (node (ref "U$13") (pin "P$6") (pinfunction "D_P$6") (pintype "passive"))
      (node (ref "U$14") (pin "P$4") (pinfunction "D_P$4") (pintype "passive"))
      (node (ref "U$14") (pin "P$6") (pinfunction "D_P$6") (pintype "passive"))
      (node (ref "U$15") (pin "P$4") (pinfunction "D_P$4") (pintype "passive"))
      (node (ref "U$15") (pin "P$6") (pinfunction "D_P$6") (pintype "passive"))
      (node (ref "U$16") (pin "P$4") (pinfunction "D_P$4") (pintype "passive"))
      (node (ref "U$16") (pin "P$6") (pinfunction "D_P$6") (pintype "passive"))
      (node (ref "U$20") (pin "P$3") (pinfunction "P$3_P$3") (pintype "bidirectional"))
      (node (ref "U$5") (pin "P$4") (pinfunction "D_P$4") (pintype "passive"))
      (node (ref "U$5") (pin "P$6") (pinfunction "D_P$6") (pintype "passive"))
      (node (ref "U$6") (pin "P$4") (pinfunction "D_P$4") (pintype "passive"))
      (node (ref "U$6") (pin "P$6") (pinfunction "D_P$6") (pintype "passive"))
      (node (ref "U$7") (pin "P$4") (pinfunction "D_P$4") (pintype "passive"))
      (node (ref "U$7") (pin "P$6") (pinfunction "D_P$6") (pintype "passive"))
      (node (ref "U$8") (pin "P$4") (pinfunction "D_P$4") (pintype "passive"))
      (node (ref "U$8") (pin "P$6") (pinfunction "D_P$6") (pintype "passive"))
      (node (ref "U$9") (pin "P$4") (pinfunction "D_P$4") (pintype "passive"))
      (node (ref "U$9") (pin "P$6") (pinfunction "D_P$6") (pintype "passive"))
    )
    (net (code "3") (name "GND") (class "Default")
      (node (ref "C1") (pin "2") (pinfunction "2_2") (pintype "passive"))
      (node (ref "C10") (pin "2") (pinfunction "2_2") (pintype "passive"))
      (node (ref "C11") (pin "2") (pinfunction "2_2") (pintype "passive"))
      (node (ref "C12") (pin "2") (pinfunction "2_2") (pintype "passive"))
      (node (ref "C13") (pin "2") (pinfunction "2_2") (pintype "passive"))
      (node (ref "C14") (pin "2") (pinfunction "2_2") (pintype "passive"))
      (node (ref "C15") (pin "2") (pinfunction "2_2") (pintype "passive"))
      (node (ref "C16") (pin "2") (pinfunction "2_2") (pintype "passive"))
      (node (ref "C17") (pin "2") (pinfunction "2_2") (pintype "passive"))
      (node (ref "C18") (pin "2") (pinfunction "2_2") (pintype "passive"))
      (node (ref "C19") (pin "2") (pinfunction "2_2") (pintype "passive"))
      (node (ref "C2") (pin "2") (pinfunction "2_2") (pintype "passive"))
      (node (ref "C20") (pin "2") (pinfunction "2_2") (pintype "passive"))
      (node (ref "C21") (pin "2") (pinfunction "2_2") (pintype "passive"))
      (node (ref "C22") (pin "2") (pinfunction "2_2") (pintype "passive"))
      (node (ref "C23") (pin "2") (pinfunction "2_2") (pintype "passive"))
      (node (ref "C24") (pin "2") (pinfunction "2_2") (pintype "passive"))
      (node (ref "C25") (pin "2") (pinfunction "2_2") (pintype "passive"))
      (node (ref "C26") (pin "2") (pinfunction "2_2") (pintype "passive"))
      (node (ref "C27") (pin "2") (pinfunction "2_2") (pintype "passive"))
      (node (ref "C28") (pin "2") (pinfunction "2_2") (pintype "passive"))
      (node (ref "C29") (pin "P-") (pinfunction "P-_P-") (pintype "passive"))
      (node (ref "C3") (pin "2") (pinfunction "2_2") (pintype "passive"))
      (node (ref "C30") (pin "2") (pinfunction "2_2") (pintype "passive"))
      (node (ref "C31") (pin "2") (pinfunction "2_2") (pintype "passive"))
      (node (ref "C32") (pin "2") (pinfunction "2_2") (pintype "passive"))
      (node (ref "C33") (pin "1") (pinfunction "1_1") (pintype "passive"))
      (node (ref "C4") (pin "2") (pinfunction "2_2") (pintype "passive"))
      (node (ref "C5") (pin "2") (pinfunction "2_2") (pintype "passive"))
      (node (ref "C6") (pin "2") (pinfunction "2_2") (pintype "passive"))
      (node (ref "C7") (pin "2") (pinfunction "2_2") (pintype "passive"))
      (node (ref "C8") (pin "2") (pinfunction "2_2") (pintype "passive"))
      (node (ref "C9") (pin "2") (pinfunction "2_2") (pintype "passive"))
      (node (ref "CANIC") (pin "2") (pinfunction "VSS_2") (pintype "power_in"))
      (node (ref "CANIC") (pin "8") (pinfunction "RS_8") (pintype "input"))
      (node (ref "CN3") (pin "1") (pinfunction "1_1") (pintype "passive"))
      (node (ref "CN3") (pin "2") (pinfunction "2_2") (pintype "passive"))
      (node (ref "CN_TANIT") (pin "1") (pinfunction "1_1") (pintype "passive"))
      (node (ref "IC1") (pin "2") (pinfunction "GND_2") (pintype "bidirectional"))
      (node (ref "IC2") (pin "2") (pinfunction "GND_2") (pintype "bidirectional"))
      (node (ref "IC3") (pin "2") (pinfunction "GND_2") (pintype "bidirectional"))
      (node (ref "IC4") (pin "2") (pinfunction "GND_2") (pintype "bidirectional"))
      (node (ref "IC5") (pin "2") (pinfunction "GND_2") (pintype "bidirectional"))
      (node (ref "IC6") (pin "2") (pinfunction "GND_2") (pintype "bidirectional"))
      (node (ref "IC7") (pin "1") (pinfunction "01_GND_1") (pintype "power_in"))
      (node (ref "IC7") (pin "13") (pinfunction "13_~{OE}_13") (pintype "input"))
      (node (ref "IC8") (pin "1") (pinfunction "01_GND_1") (pintype "power_in"))
      (node (ref "IC8") (pin "13") (pinfunction "13_~{OE}_13") (pintype "input"))
      (node (ref "IC9") (pin "1") (pinfunction "01_GND_1") (pintype "power_in"))
      (node (ref "IC9") (pin "13") (pinfunction "13_~{OE}_13") (pintype "input"))
      (node (ref "PIC1") (pin "29") (pinfunction "VSS_29") (pintype "power_in"))
      (node (ref "PIC1") (pin "6") (pinfunction "VSS_2_6") (pintype "power_in"))
      (node (ref "R2") (pin "1") (pinfunction "A_1") (pintype "passive"))
      (node (ref "R3") (pin "1") (pinfunction "A_1") (pintype "passive"))
      (node (ref "R4") (pin "1") (pinfunction "A_1") (pintype "passive"))
      (node (ref "STAB1") (pin "3") (pinfunction "GND_3") (pintype "passive"))
      (node (ref "U$20") (pin "P$1") (pinfunction "P$1_P$1") (pintype "bidirectional"))
      (node (ref "XT1") (pin "2") (pinfunction "2_2") (pintype "passive"))
      (node (ref "XT1") (pin "4") (pinfunction "4_4") (pintype "passive"))
      (node (ref "ZOLD_3P1") (pin "1") (pinfunction "1_1") (pintype "passive"))
      (node (ref "ZOLD_3P10") (pin "1") (pinfunction "1_1") (pintype "passive"))
      (node (ref "ZOLD_3P11") (pin "1") (pinfunction "1_1") (pintype "passive"))
      (node (ref "ZOLD_3P12") (pin "1") (pinfunction "1_1") (pintype "passive"))
      (node (ref "ZOLD_3P2") (pin "1") (pinfunction "1_1") (pintype "passive"))
      (node (ref "ZOLD_3P3") (pin "1") (pinfunction "1_1") (pintype "passive"))
      (node (ref "ZOLD_3P4") (pin "1") (pinfunction "1_1") (pintype "passive"))
      (node (ref "ZOLD_3P5") (pin "1") (pinfunction "1_1") (pintype "passive"))
      (node (ref "ZOLD_3P6") (pin "1") (pinfunction "1_1") (pintype "passive"))
      (node (ref "ZOLD_3P7") (pin "1") (pinfunction "1_1") (pintype "passive"))
      (node (ref "ZOLD_3P8") (pin "1") (pinfunction "1_1") (pintype "passive"))
      (node (ref "ZOLD_3P9") (pin "1") (pinfunction "1_1") (pintype "passive"))
    )
    (net (code "4") (name "Net-(CANIC-CANH)") (class "Default")
      (node (ref "CANIC") (pin "7") (pinfunction "CANH_7") (pintype "bidirectional"))
      (node (ref "CN_CANLEZAR") (pin "2") (pinfunction "2_2") (pintype "passive"))
      (node (ref "CN_RJ1") (pin "4") (pinfunction "4_4") (pintype "passive"))
      (node (ref "CN_RJ2") (pin "4") (pinfunction "4_4") (pintype "passive"))
    )
    (net (code "5") (name "Net-(CANIC-CANL)") (class "Default")
      (node (ref "CANIC") (pin "6") (pinfunction "CANL_6") (pintype "bidirectional"))
      (node (ref "CN_RJ1") (pin "5") (pinfunction "5_5") (pintype "passive"))
      (node (ref "CN_RJ2") (pin "5") (pinfunction "5_5") (pintype "passive"))
      (node (ref "R125") (pin "1") (pinfunction "A_1") (pintype "passive"))
      (node (ref "R126") (pin "2") (pinfunction "E_2") (pintype "passive"))
    )
    (net (code "6") (name "Net-(CANIC-RXD)") (class "Default")
      (node (ref "CANIC") (pin "4") (pinfunction "RXD_4") (pintype "output"))
      (node (ref "PIC1") (pin "11") (pinfunction "RB3/CANRX_11") (pintype "bidirectional"))
    )
    (net (code "7") (name "Net-(CANIC-TXD)") (class "Default")
      (node (ref "CANIC") (pin "1") (pinfunction "TXD_1") (pintype "input"))
      (node (ref "PIC1") (pin "10") (pinfunction "RB2/INT2/CANTX_10") (pintype "bidirectional"))
    )
    (net (code "8") (name "Net-(CN3-Pad10)") (class "Default")
      (node (ref "CN3") (pin "10") (pinfunction "10_10") (pintype "passive"))
      (node (ref "CN3") (pin "9") (pinfunction "9_9") (pintype "passive"))
    )
    (net (code "9") (name "Net-(CN_RJ1-Pad7)") (class "Default")
      (node (ref "CN_RJ1") (pin "7") (pinfunction "7_7") (pintype "passive"))
      (node (ref "CN_RJ2") (pin "7") (pinfunction "7_7") (pintype "passive"))
      (node (ref "U$21") (pin "P$1") (pinfunction "P$1_P$1") (pintype "bidirectional"))
    )
    (net (code "10") (name "Net-(CN_RJ1-Pad8)") (class "Default")
      (node (ref "CN_RJ1") (pin "8") (pinfunction "8_8") (pintype "passive"))
      (node (ref "D1") (pin "C") (pinfunction "C_C") (pintype "passive"))
    )
    (net (code "11") (name "Net-(CN_RJ2-Pad8)") (class "Default")
      (node (ref "CN_RJ2") (pin "8") (pinfunction "8_8") (pintype "passive"))
      (node (ref "D2") (pin "C") (pinfunction "C_C") (pintype "passive"))
    )
    (net (code "12") (name "Net-(D1-PadA)") (class "Default")
      (node (ref "D1") (pin "A") (pinfunction "A_A") (pintype "passive"))
      (node (ref "D2") (pin "A") (pinfunction "A_A") (pintype "passive"))
      (node (ref "U$21") (pin "P$2") (pinfunction "P$2_P$2") (pintype "bidirectional"))
    )
    (net (code "13") (name "Net-(IC1-I{slash}O1)") (class "Default")
      (node (ref "C4") (pin "1") (pinfunction "1_1") (pintype "passive"))
      (node (ref "IC1") (pin "1") (pinfunction "I/O1_1") (pintype "bidirectional"))
      (node (ref "R101") (pin "2") (pinfunction "E_2") (pintype "passive"))
      (node (ref "R53") (pin "1") (pinfunction "A_1") (pintype "passive"))
    )
    (net (code "14") (name "Net-(IC1-I{slash}O2)") (class "Default")
      (node (ref "C5") (pin "1") (pinfunction "1_1") (pintype "passive"))
      (node (ref "IC1") (pin "3") (pinfunction "I/O2_3") (pintype "bidirectional"))
      (node (ref "R102") (pin "2") (pinfunction "E_2") (pintype "passive"))
      (node (ref "R54") (pin "1") (pinfunction "A_1") (pintype "passive"))
    )
    (net (code "15") (name "Net-(IC1-I{slash}O3)") (class "Default")
      (node (ref "C6") (pin "1") (pinfunction "1_1") (pintype "passive"))
      (node (ref "IC1") (pin "4") (pinfunction "I/O3_4") (pintype "bidirectional"))
      (node (ref "R103") (pin "2") (pinfunction "E_2") (pintype "passive"))
      (node (ref "R55") (pin "1") (pinfunction "A_1") (pintype "passive"))
    )
    (net (code "16") (name "Net-(IC1-I{slash}O4)") (class "Default")
      (node (ref "C7") (pin "1") (pinfunction "1_1") (pintype "passive"))
      (node (ref "IC1") (pin "6") (pinfunction "I/O4_6") (pintype "bidirectional"))
      (node (ref "R104") (pin "2") (pinfunction "E_2") (pintype "passive"))
      (node (ref "R56") (pin "1") (pinfunction "A_1") (pintype "passive"))
    )
    (net (code "17") (name "Net-(IC2-I{slash}O1)") (class "Default")
      (node (ref "C8") (pin "1") (pinfunction "1_1") (pintype "passive"))
      (node (ref "IC2") (pin "1") (pinfunction "I/O1_1") (pintype "bidirectional"))
      (node (ref "R105") (pin "2") (pinfunction "E_2") (pintype "passive"))
      (node (ref "R57") (pin "1") (pinfunction "A_1") (pintype "passive"))
    )
    (net (code "18") (name "Net-(IC2-I{slash}O2)") (class "Default")
      (node (ref "C9") (pin "1") (pinfunction "1_1") (pintype "passive"))
      (node (ref "IC2") (pin "3") (pinfunction "I/O2_3") (pintype "bidirectional"))
      (node (ref "R106") (pin "2") (pinfunction "E_2") (pintype "passive"))
      (node (ref "R58") (pin "1") (pinfunction "A_1") (pintype "passive"))
    )
    (net (code "19") (name "Net-(IC2-I{slash}O3)") (class "Default")
      (node (ref "C10") (pin "1") (pinfunction "1_1") (pintype "passive"))
      (node (ref "IC2") (pin "4") (pinfunction "I/O3_4") (pintype "bidirectional"))
      (node (ref "R107") (pin "2") (pinfunction "E_2") (pintype "passive"))
      (node (ref "R59") (pin "1") (pinfunction "A_1") (pintype "passive"))
    )
    (net (code "20") (name "Net-(IC2-I{slash}O4)") (class "Default")
      (node (ref "C11") (pin "1") (pinfunction "1_1") (pintype "passive"))
      (node (ref "IC2") (pin "6") (pinfunction "I/O4_6") (pintype "bidirectional"))
      (node (ref "R108") (pin "2") (pinfunction "E_2") (pintype "passive"))
      (node (ref "R60") (pin "1") (pinfunction "A_1") (pintype "passive"))
    )
    (net (code "21") (name "Net-(IC3-I{slash}O1)") (class "Default")
      (node (ref "C12") (pin "1") (pinfunction "1_1") (pintype "passive"))
      (node (ref "IC3") (pin "1") (pinfunction "I/O1_1") (pintype "bidirectional"))
      (node (ref "R109") (pin "2") (pinfunction "E_2") (pintype "passive"))
      (node (ref "R61") (pin "1") (pinfunction "A_1") (pintype "passive"))
    )
    (net (code "22") (name "Net-(IC3-I{slash}O2)") (class "Default")
      (node (ref "C13") (pin "1") (pinfunction "1_1") (pintype "passive"))
      (node (ref "IC3") (pin "3") (pinfunction "I/O2_3") (pintype "bidirectional"))
      (node (ref "R110") (pin "2") (pinfunction "E_2") (pintype "passive"))
      (node (ref "R62") (pin "1") (pinfunction "A_1") (pintype "passive"))
    )
    (net (code "23") (name "Net-(IC3-I{slash}O3)") (class "Default")
      (node (ref "C14") (pin "1") (pinfunction "1_1") (pintype "passive"))
      (node (ref "IC3") (pin "4") (pinfunction "I/O3_4") (pintype "bidirectional"))
      (node (ref "R111") (pin "2") (pinfunction "E_2") (pintype "passive"))
      (node (ref "R63") (pin "1") (pinfunction "A_1") (pintype "passive"))
    )
    (net (code "24") (name "Net-(IC3-I{slash}O4)") (class "Default")
      (node (ref "C15") (pin "1") (pinfunction "1_1") (pintype "passive"))
      (node (ref "IC3") (pin "6") (pinfunction "I/O4_6") (pintype "bidirectional"))
      (node (ref "R112") (pin "2") (pinfunction "E_2") (pintype "passive"))
      (node (ref "R64") (pin "1") (pinfunction "A_1") (pintype "passive"))
    )
    (net (code "25") (name "Net-(IC4-I{slash}O1)") (class "Default")
      (node (ref "C16") (pin "1") (pinfunction "1_1") (pintype "passive"))
      (node (ref "IC4") (pin "1") (pinfunction "I/O1_1") (pintype "bidirectional"))
      (node (ref "R113") (pin "2") (pinfunction "E_2") (pintype "passive"))
      (node (ref "R65") (pin "1") (pinfunction "A_1") (pintype "passive"))
    )
    (net (code "26") (name "Net-(IC4-I{slash}O2)") (class "Default")
      (node (ref "C17") (pin "1") (pinfunction "1_1") (pintype "passive"))
      (node (ref "IC4") (pin "3") (pinfunction "I/O2_3") (pintype "bidirectional"))
      (node (ref "R114") (pin "2") (pinfunction "E_2") (pintype "passive"))
      (node (ref "R66") (pin "1") (pinfunction "A_1") (pintype "passive"))
    )
    (net (code "27") (name "Net-(IC4-I{slash}O3)") (class "Default")
      (node (ref "C18") (pin "1") (pinfunction "1_1") (pintype "passive"))
      (node (ref "IC4") (pin "4") (pinfunction "I/O3_4") (pintype "bidirectional"))
      (node (ref "R115") (pin "2") (pinfunction "E_2") (pintype "passive"))
      (node (ref "R67") (pin "1") (pinfunction "A_1") (pintype "passive"))
    )
    (net (code "28") (name "Net-(IC4-I{slash}O4)") (class "Default")
      (node (ref "C19") (pin "1") (pinfunction "1_1") (pintype "passive"))
      (node (ref "IC4") (pin "6") (pinfunction "I/O4_6") (pintype "bidirectional"))
      (node (ref "R116") (pin "2") (pinfunction "E_2") (pintype "passive"))
      (node (ref "R68") (pin "1") (pinfunction "A_1") (pintype "passive"))
    )
    (net (code "29") (name "Net-(IC5-I{slash}O1)") (class "Default")
      (node (ref "C20") (pin "1") (pinfunction "1_1") (pintype "passive"))
      (node (ref "IC5") (pin "1") (pinfunction "I/O1_1") (pintype "bidirectional"))
      (node (ref "R117") (pin "2") (pinfunction "E_2") (pintype "passive"))
      (node (ref "R69") (pin "1") (pinfunction "A_1") (pintype "passive"))
    )
    (net (code "30") (name "Net-(IC5-I{slash}O2)") (class "Default")
      (node (ref "C21") (pin "1") (pinfunction "1_1") (pintype "passive"))
      (node (ref "IC5") (pin "3") (pinfunction "I/O2_3") (pintype "bidirectional"))
      (node (ref "R118") (pin "2") (pinfunction "E_2") (pintype "passive"))
      (node (ref "R70") (pin "1") (pinfunction "A_1") (pintype "passive"))
    )
    (net (code "31") (name "Net-(IC5-I{slash}O3)") (class "Default")
      (node (ref "C22") (pin "1") (pinfunction "1_1") (pintype "passive"))
      (node (ref "IC5") (pin "4") (pinfunction "I/O3_4") (pintype "bidirectional"))
      (node (ref "R119") (pin "2") (pinfunction "E_2") (pintype "passive"))
      (node (ref "R71") (pin "1") (pinfunction "A_1") (pintype "passive"))
    )
    (net (code "32") (name "Net-(IC5-I{slash}O4)") (class "Default")
      (node (ref "C23") (pin "1") (pinfunction "1_1") (pintype "passive"))
      (node (ref "IC5") (pin "6") (pinfunction "I/O4_6") (pintype "bidirectional"))
      (node (ref "R120") (pin "2") (pinfunction "E_2") (pintype "passive"))
      (node (ref "R72") (pin "1") (pinfunction "A_1") (pintype "passive"))
    )
    (net (code "33") (name "Net-(IC6-I{slash}O1)") (class "Default")
      (node (ref "C24") (pin "1") (pinfunction "1_1") (pintype "passive"))
      (node (ref "IC6") (pin "1") (pinfunction "I/O1_1") (pintype "bidirectional"))
      (node (ref "R121") (pin "2") (pinfunction "E_2") (pintype "passive"))
      (node (ref "R73") (pin "1") (pinfunction "A_1") (pintype "passive"))
    )
    (net (code "34") (name "Net-(IC6-I{slash}O2)") (class "Default")
      (node (ref "C25") (pin "1") (pinfunction "1_1") (pintype "passive"))
      (node (ref "IC6") (pin "3") (pinfunction "I/O2_3") (pintype "bidirectional"))
      (node (ref "R122") (pin "2") (pinfunction "E_2") (pintype "passive"))
      (node (ref "R74") (pin "1") (pinfunction "A_1") (pintype "passive"))
    )
    (net (code "35") (name "Net-(IC6-I{slash}O3)") (class "Default")
      (node (ref "C26") (pin "1") (pinfunction "1_1") (pintype "passive"))
      (node (ref "IC6") (pin "4") (pinfunction "I/O3_4") (pintype "bidirectional"))
      (node (ref "R123") (pin "2") (pinfunction "E_2") (pintype "passive"))
      (node (ref "R75") (pin "1") (pinfunction "A_1") (pintype "passive"))
    )
    (net (code "36") (name "Net-(IC6-I{slash}O4)") (class "Default")
      (node (ref "C27") (pin "1") (pinfunction "1_1") (pintype "passive"))
      (node (ref "IC6") (pin "6") (pinfunction "I/O4_6") (pintype "bidirectional"))
      (node (ref "R124") (pin "2") (pinfunction "E_2") (pintype "passive"))
      (node (ref "R76") (pin "1") (pinfunction "A_1") (pintype "passive"))
    )
    (net (code "37") (name "Net-(IC7-02_SDI)") (class "Default")
      (node (ref "IC7") (pin "2") (pinfunction "02_SDI_2") (pintype "input"))
      (node (ref "PIC1") (pin "43") (pinfunction "RC5/SDO_43") (pintype "bidirectional"))
    )
    (net (code "38") (name "Net-(IC7-03_CLK)") (class "Default")
      (node (ref "IC7") (pin "3") (pinfunction "03_CLK_3") (pintype "input"))
      (node (ref "IC8") (pin "3") (pinfunction "03_CLK_3") (pintype "input"))
      (node (ref "IC9") (pin "3") (pinfunction "03_CLK_3") (pintype "input"))
      (node (ref "PIC1") (pin "37") (pinfunction "RC3/SCK/SCL_37") (pintype "bidirectional"))
    )
    (net (code "39") (name "Net-(IC7-04_~{LA})") (class "Default")
      (node (ref "IC7") (pin "4") (pinfunction "04_~{LA}_4") (pintype "input"))
      (node (ref "IC8") (pin "4") (pinfunction "04_~{LA}_4") (pintype "input"))
      (node (ref "IC9") (pin "4") (pinfunction "04_~{LA}_4") (pintype "input"))
      (node (ref "PIC1") (pin "36") (pinfunction "RC2/CCP1_36") (pintype "bidirectional"))
    )
    (net (code "40") (name "Net-(IC7-05_OUT0)") (class "Default")
      (node (ref "IC7") (pin "5") (pinfunction "05_OUT0_5") (pintype "output"))
      (node (ref "R5") (pin "2") (pinfunction "E_2") (pintype "passive"))
      (node (ref "U$5") (pin "P$1") (pinfunction "G_P$1") (pintype "passive"))
    )
    (net (code "41") (name "Net-(IC7-06_OUT1)") (class "Default")
      (node (ref "IC7") (pin "6") (pinfunction "06_OUT1_6") (pintype "output"))
      (node (ref "R6") (pin "2") (pinfunction "E_2") (pintype "passive"))
      (node (ref "U$5") (pin "P$3") (pinfunction "G_P$3") (pintype "passive"))
    )
    (net (code "42") (name "Net-(IC7-07_OUT2)") (class "Default")
      (node (ref "IC7") (pin "7") (pinfunction "07_OUT2_7") (pintype "output"))
      (node (ref "R7") (pin "2") (pinfunction "E_2") (pintype "passive"))
      (node (ref "U$6") (pin "P$1") (pinfunction "G_P$1") (pintype "passive"))
    )
    (net (code "43") (name "Net-(IC7-08_OUT3)") (class "Default")
      (node (ref "IC7") (pin "8") (pinfunction "08_OUT3_8") (pintype "output"))
      (node (ref "R8") (pin "2") (pinfunction "E_2") (pintype "passive"))
      (node (ref "U$6") (pin "P$3") (pinfunction "G_P$3") (pintype "passive"))
    )
    (net (code "44") (name "Net-(IC7-09_OUT4)") (class "Default")
      (node (ref "IC7") (pin "9") (pinfunction "09_OUT4_9") (pintype "output"))
      (node (ref "R9") (pin "2") (pinfunction "E_2") (pintype "passive"))
      (node (ref "U$7") (pin "P$1") (pinfunction "G_P$1") (pintype "passive"))
    )
    (net (code "45") (name "Net-(IC7-10_OUT5)") (class "Default")
      (node (ref "IC7") (pin "10") (pinfunction "10_OUT5_10") (pintype "output"))
      (node (ref "R10") (pin "2") (pinfunction "E_2") (pintype "passive"))
      (node (ref "U$7") (pin "P$3") (pinfunction "G_P$3") (pintype "passive"))
    )
    (net (code "46") (name "Net-(IC7-11_OUT6)") (class "Default")
      (node (ref "IC7") (pin "11") (pinfunction "11_OUT6_11") (pintype "output"))
      (node (ref "R11") (pin "2") (pinfunction "E_2") (pintype "passive"))
      (node (ref "U$8") (pin "P$1") (pinfunction "G_P$1") (pintype "passive"))
    )
    (net (code "47") (name "Net-(IC7-12_OUT7)") (class "Default")
      (node (ref "IC7") (pin "12") (pinfunction "12_OUT7_12") (pintype "output"))
      (node (ref "R12") (pin "2") (pinfunction "E_2") (pintype "passive"))
      (node (ref "U$8") (pin "P$3") (pinfunction "G_P$3") (pintype "passive"))
    )
    (net (code "48") (name "Net-(IC7-14_SDO)") (class "Default")
      (node (ref "IC7") (pin "14") (pinfunction "14_SDO_14") (pintype "output"))
      (node (ref "IC8") (pin "2") (pinfunction "02_SDI_2") (pintype "input"))
    )
    (net (code "49") (name "Net-(IC7-15_REXT)") (class "Default")
      (node (ref "IC7") (pin "15") (pinfunction "15_REXT_15") (pintype "bidirectional"))
      (node (ref "R2") (pin "2") (pinfunction "E_2") (pintype "passive"))
    )
    (net (code "50") (name "Net-(IC8-05_OUT0)") (class "Default")
      (node (ref "IC8") (pin "5") (pinfunction "05_OUT0_5") (pintype "output"))
      (node (ref "R13") (pin "2") (pinfunction "E_2") (pintype "passive"))
      (node (ref "U$9") (pin "P$1") (pinfunction "G_P$1") (pintype "passive"))
    )
    (net (code "51") (name "Net-(IC8-06_OUT1)") (class "Default")
      (node (ref "IC8") (pin "6") (pinfunction "06_OUT1_6") (pintype "output"))
      (node (ref "R14") (pin "2") (pinfunction "E_2") (pintype "passive"))
      (node (ref "U$9") (pin "P$3") (pinfunction "G_P$3") (pintype "passive"))
    )
    (net (code "52") (name "Net-(IC8-07_OUT2)") (class "Default")
      (node (ref "IC8") (pin "7") (pinfunction "07_OUT2_7") (pintype "output"))
      (node (ref "R15") (pin "2") (pinfunction "E_2") (pintype "passive"))
      (node (ref "U$10") (pin "P$1") (pinfunction "G_P$1") (pintype "passive"))
    )
    (net (code "53") (name "Net-(IC8-08_OUT3)") (class "Default")
      (node (ref "IC8") (pin "8") (pinfunction "08_OUT3_8") (pintype "output"))
      (node (ref "R16") (pin "2") (pinfunction "E_2") (pintype "passive"))
      (node (ref "U$10") (pin "P$3") (pinfunction "G_P$3") (pintype "passive"))
    )
    (net (code "54") (name "Net-(IC8-09_OUT4)") (class "Default")
      (node (ref "IC8") (pin "9") (pinfunction "09_OUT4_9") (pintype "output"))
      (node (ref "R17") (pin "2") (pinfunction "E_2") (pintype "passive"))
      (node (ref "U$11") (pin "P$1") (pinfunction "G_P$1") (pintype "passive"))
    )
    (net (code "55") (name "Net-(IC8-10_OUT5)") (class "Default")
      (node (ref "IC8") (pin "10") (pinfunction "10_OUT5_10") (pintype "output"))
      (node (ref "R18") (pin "2") (pinfunction "E_2") (pintype "passive"))
      (node (ref "U$11") (pin "P$3") (pinfunction "G_P$3") (pintype "passive"))
    )
    (net (code "56") (name "Net-(IC8-11_OUT6)") (class "Default")
      (node (ref "IC8") (pin "11") (pinfunction "11_OUT6_11") (pintype "output"))
      (node (ref "R19") (pin "2") (pinfunction "E_2") (pintype "passive"))
      (node (ref "U$12") (pin "P$1") (pinfunction "G_P$1") (pintype "passive"))
    )
    (net (code "57") (name "Net-(IC8-12_OUT7)") (class "Default")
      (node (ref "IC8") (pin "12") (pinfunction "12_OUT7_12") (pintype "output"))
      (node (ref "R20") (pin "2") (pinfunction "E_2") (pintype "passive"))
      (node (ref "U$12") (pin "P$3") (pinfunction "G_P$3") (pintype "passive"))
    )
    (net (code "58") (name "Net-(IC8-14_SDO)") (class "Default")
      (node (ref "IC8") (pin "14") (pinfunction "14_SDO_14") (pintype "output"))
      (node (ref "IC9") (pin "2") (pinfunction "02_SDI_2") (pintype "input"))
    )
    (net (code "59") (name "Net-(IC8-15_REXT)") (class "Default")
      (node (ref "IC8") (pin "15") (pinfunction "15_REXT_15") (pintype "bidirectional"))
      (node (ref "R3") (pin "2") (pinfunction "E_2") (pintype "passive"))
    )
    (net (code "60") (name "Net-(IC9-05_OUT0)") (class "Default")
      (node (ref "IC9") (pin "5") (pinfunction "05_OUT0_5") (pintype "output"))
      (node (ref "R21") (pin "2") (pinfunction "E_2") (pintype "passive"))
      (node (ref "U$13") (pin "P$1") (pinfunction "G_P$1") (pintype "passive"))
    )
    (net (code "61") (name "Net-(IC9-06_OUT1)") (class "Default")
      (node (ref "IC9") (pin "6") (pinfunction "06_OUT1_6") (pintype "output"))
      (node (ref "R22") (pin "2") (pinfunction "E_2") (pintype "passive"))
      (node (ref "U$13") (pin "P$3") (pinfunction "G_P$3") (pintype "passive"))
    )
    (net (code "62") (name "Net-(IC9-07_OUT2)") (class "Default")
      (node (ref "IC9") (pin "7") (pinfunction "07_OUT2_7") (pintype "output"))
      (node (ref "R23") (pin "2") (pinfunction "E_2") (pintype "passive"))
      (node (ref "U$14") (pin "P$1") (pinfunction "G_P$1") (pintype "passive"))
    )
    (net (code "63") (name "Net-(IC9-08_OUT3)") (class "Default")
      (node (ref "IC9") (pin "8") (pinfunction "08_OUT3_8") (pintype "output"))
      (node (ref "R24") (pin "2") (pinfunction "E_2") (pintype "passive"))
      (node (ref "U$14") (pin "P$3") (pinfunction "G_P$3") (pintype "passive"))
    )
    (net (code "64") (name "Net-(IC9-09_OUT4)") (class "Default")
      (node (ref "IC9") (pin "9") (pinfunction "09_OUT4_9") (pintype "output"))
      (node (ref "R25") (pin "2") (pinfunction "E_2") (pintype "passive"))
      (node (ref "U$15") (pin "P$1") (pinfunction "G_P$1") (pintype "passive"))
    )
    (net (code "65") (name "Net-(IC9-10_OUT5)") (class "Default")
      (node (ref "IC9") (pin "10") (pinfunction "10_OUT5_10") (pintype "output"))
      (node (ref "R26") (pin "2") (pinfunction "E_2") (pintype "passive"))
      (node (ref "U$15") (pin "P$3") (pinfunction "G_P$3") (pintype "passive"))
    )
    (net (code "66") (name "Net-(IC9-11_OUT6)") (class "Default")
      (node (ref "IC9") (pin "11") (pinfunction "11_OUT6_11") (pintype "output"))
      (node (ref "R27") (pin "2") (pinfunction "E_2") (pintype "passive"))
      (node (ref "U$16") (pin "P$1") (pinfunction "G_P$1") (pintype "passive"))
    )
    (net (code "67") (name "Net-(IC9-12_OUT7)") (class "Default")
      (node (ref "IC9") (pin "12") (pinfunction "12_OUT7_12") (pintype "output"))
      (node (ref "R28") (pin "2") (pinfunction "E_2") (pintype "passive"))
      (node (ref "U$16") (pin "P$3") (pinfunction "G_P$3") (pintype "passive"))
    )
    (net (code "68") (name "Net-(IC9-15_REXT)") (class "Default")
      (node (ref "IC9") (pin "15") (pinfunction "15_REXT_15") (pintype "bidirectional"))
      (node (ref "R4") (pin "2") (pinfunction "E_2") (pintype "passive"))
    )
    (net (code "69") (name "Net-(PIC1-OSC1{slash}CLKI{slash}RA7)") (class "Default")
      (node (ref "C2") (pin "1") (pinfunction "1_1") (pintype "passive"))
      (node (ref "PIC1") (pin "30") (pinfunction "OSC1/CLKI/RA7_30") (pintype "bidirectional"))
      (node (ref "XT1") (pin "3") (pinfunction "3_3") (pintype "passive"))
    )
    (net (code "70") (name "Net-(PIC1-OSC2{slash}CLKO{slash}RA6)") (class "Default")
      (node (ref "C1") (pin "1") (pinfunction "1_1") (pintype "passive"))
      (node (ref "PIC1") (pin "31") (pinfunction "OSC2/CLKO/RA6_31") (pintype "bidirectional"))
      (node (ref "XT1") (pin "1") (pinfunction "1_1") (pintype "passive"))
    )
    (net (code "71") (name "Net-(PIC1-RA0{slash}AN0{slash}CVREF)") (class "Default")
      (node (ref "PIC1") (pin "19") (pinfunction "RA0/AN0/CVREF_19") (pintype "bidirectional"))
      (node (ref "R112") (pin "1") (pinfunction "A_1") (pintype "passive"))
    )
    (net (code "72") (name "Net-(PIC1-RA1{slash}AN1)") (class "Default")
      (node (ref "PIC1") (pin "20") (pinfunction "RA1/AN1_20") (pintype "bidirectional"))
      (node (ref "R113") (pin "1") (pinfunction "A_1") (pintype "passive"))
    )
    (net (code "73") (name "Net-(PIC1-RA2{slash}AN2{slash}VREF-)") (class "Default")
      (node (ref "PIC1") (pin "21") (pinfunction "RA2/AN2/VREF-_21") (pintype "bidirectional"))
      (node (ref "R107") (pin "1") (pinfunction "A_1") (pintype "passive"))
    )
    (net (code "74") (name "Net-(PIC1-RA3{slash}AN3{slash}VREF+)") (class "Default")
      (node (ref "PIC1") (pin "22") (pinfunction "RA3/AN3/VREF+_22") (pintype "bidirectional"))
      (node (ref "R116") (pin "1") (pinfunction "A_1") (pintype "passive"))
    )
    (net (code "75") (name "Net-(PIC1-RA5{slash}AN4{slash}~{SS{slash}HLVDIN})") (class "Default")
      (node (ref "PIC1") (pin "24") (pinfunction "RA5/AN4/~{SS/HLVDIN}_24") (pintype "bidirectional"))
      (node (ref "R108") (pin "1") (pinfunction "A_1") (pintype "passive"))
    )
    (net (code "76") (name "Net-(PIC1-RB0{slash}INT0{slash}FLT0{slash}AN10)") (class "Default")
      (node (ref "PIC1") (pin "8") (pinfunction "RB0/INT0/FLT0/AN10_8") (pintype "bidirectional"))
      (node (ref "R122") (pin "1") (pinfunction "A_1") (pintype "passive"))
    )
    (net (code "77") (name "Net-(PIC1-RB1{slash}INT1{slash}AN8)") (class "Default")
      (node (ref "PIC1") (pin "9") (pinfunction "RB1/INT1/AN8_9") (pintype "bidirectional"))
      (node (ref "R123") (pin "1") (pinfunction "A_1") (pintype "passive"))
    )
    (net (code "78") (name "Net-(PIC1-RB4{slash}KBI0{slash}AN9)") (class "Default")
      (node (ref "PIC1") (pin "14") (pinfunction "RB4/KBI0/AN9_14") (pintype "bidirectional"))
      (node (ref "R124") (pin "1") (pinfunction "A_1") (pintype "passive"))
    )
    (net (code "79") (name "Net-(PIC1-RB5{slash}KBI1{slash}PGM)") (class "Default")
      (node (ref "PIC1") (pin "15") (pinfunction "RB5/KBI1/PGM_15") (pintype "bidirectional"))
      (node (ref "R109") (pin "1") (pinfunction "A_1") (pintype "passive"))
    )
    (net (code "80") (name "Net-(PIC1-RB6{slash}KBI2{slash}PGC)") (class "Default")
      (node (ref "CN3") (pin "5") (pinfunction "5_5") (pintype "passive"))
      (node (ref "CN3") (pin "6") (pinfunction "6_6") (pintype "passive"))
      (node (ref "CN_TANIT") (pin "5") (pinfunction "5_5") (pintype "passive"))
      (node (ref "PIC1") (pin "16") (pinfunction "RB6/KBI2/PGC_16") (pintype "bidirectional"))
    )
    (net (code "81") (name "Net-(PIC1-RB7{slash}KBI3{slash}PGD)") (class "Default")
      (node (ref "CN3") (pin "7") (pinfunction "7_7") (pintype "passive"))
      (node (ref "CN3") (pin "8") (pinfunction "8_8") (pintype "passive"))
      (node (ref "CN_TANIT") (pin "4") (pinfunction "4_4") (pintype "passive"))
      (node (ref "PIC1") (pin "17") (pinfunction "RB7/KBI3/PGD_17") (pintype "bidirectional"))
    )
    (net (code "82") (name "Net-(PIC1-RC0{slash}T1OSO{slash}T13CKI)") (class "Default")
      (node (ref "PIC1") (pin "32") (pinfunction "RC0/T1OSO/T13CKI_32") (pintype "bidirectional"))
      (node (ref "R114") (pin "1") (pinfunction "A_1") (pintype "passive"))
    )
    (net (code "83") (name "Net-(PIC1-RC1{slash}T1OSI)") (class "Default")
      (node (ref "PIC1") (pin "35") (pinfunction "RC1/T1OSI_35") (pintype "bidirectional"))
      (node (ref "R115") (pin "1") (pinfunction "A_1") (pintype "passive"))
    )
    (net (code "84") (name "Net-(PIC1-RC4{slash}SDI{slash}SDA)") (class "Default")
      (node (ref "PIC1") (pin "42") (pinfunction "RC4/SDI/SDA_42") (pintype "bidirectional"))
      (node (ref "R102") (pin "1") (pinfunction "A_1") (pintype "passive"))
    )
    (net (code "85") (name "Net-(PIC1-RC6{slash}TX{slash}CK)") (class "Default")
      (node (ref "PIC1") (pin "44") (pinfunction "RC6/TX/CK_44") (pintype "bidirectional"))
      (node (ref "R101") (pin "1") (pinfunction "A_1") (pintype "passive"))
    )
    (net (code "86") (name "Net-(PIC1-RC7{slash}RX{slash}DT)") (class "Default")
      (node (ref "PIC1") (pin "1") (pinfunction "RC7/RX/DT_1") (pintype "bidirectional"))
      (node (ref "R117") (pin "1") (pinfunction "A_1") (pintype "passive"))
    )
    (net (code "87") (name "Net-(PIC1-RD0{slash}PSP0{slash}C1IN+)") (class "Default")
      (node (ref "PIC1") (pin "38") (pinfunction "RD0/PSP0/C1IN+_38") (pintype "bidirectional"))
      (node (ref "R104") (pin "1") (pinfunction "A_1") (pintype "passive"))
    )
    (net (code "88") (name "Net-(PIC1-RD1{slash}PSP1{slash}C1IN-)") (class "Default")
      (node (ref "PIC1") (pin "39") (pinfunction "RD1/PSP1/C1IN-_39") (pintype "bidirectional"))
      (node (ref "R103") (pin "1") (pinfunction "A_1") (pintype "passive"))
    )
    (net (code "89") (name "Net-(PIC1-RD2{slash}PSP2{slash}C2IN+)") (class "Default")
      (node (ref "PIC1") (pin "40") (pinfunction "RD2/PSP2/C2IN+_40") (pintype "bidirectional"))
      (node (ref "R111") (pin "1") (pinfunction "A_1") (pintype "passive"))
    )
    (net (code "90") (name "Net-(PIC1-RD3{slash}PSP3{slash}C2IN-)") (class "Default")
      (node (ref "PIC1") (pin "41") (pinfunction "RD3/PSP3/C2IN-_41") (pintype "bidirectional"))
      (node (ref "R110") (pin "1") (pinfunction "A_1") (pintype "passive"))
    )
    (net (code "91") (name "Net-(PIC1-RD4{slash}PSP4{slash}ECCP1{slash}P1A)") (class "Default")
      (node (ref "PIC1") (pin "2") (pinfunction "RD4/PSP4/ECCP1/P1A_2") (pintype "bidirectional"))
      (node (ref "R118") (pin "1") (pinfunction "A_1") (pintype "passive"))
    )
    (net (code "92") (name "Net-(PIC1-RD5{slash}PSP5{slash}P1B)") (class "Default")
      (node (ref "PIC1") (pin "3") (pinfunction "RD5/PSP5/P1B_3") (pintype "bidirectional"))
      (node (ref "R119") (pin "1") (pinfunction "A_1") (pintype "passive"))
    )
    (net (code "93") (name "Net-(PIC1-RD6{slash}PSP6{slash}P1C)") (class "Default")
      (node (ref "PIC1") (pin "4") (pinfunction "RD6/PSP6/P1C_4") (pintype "bidirectional"))
      (node (ref "R120") (pin "1") (pinfunction "A_1") (pintype "passive"))
    )
    (net (code "94") (name "Net-(PIC1-RD7{slash}PSP7{slash}P1D)") (class "Default")
      (node (ref "PIC1") (pin "5") (pinfunction "RD7/PSP7/P1D_5") (pintype "bidirectional"))
      (node (ref "R121") (pin "1") (pinfunction "A_1") (pintype "passive"))
    )
    (net (code "95") (name "Net-(PIC1-RE1{slash}~{WR{slash}AN6{slash}C1OUT})") (class "Default")
      (node (ref "PIC1") (pin "26") (pinfunction "RE1/~{WR/AN6/C1OUT}_26") (pintype "bidirectional"))
      (node (ref "R106") (pin "1") (pinfunction "A_1") (pintype "passive"))
    )
    (net (code "96") (name "Net-(PIC1-RE2{slash}~{CS{slash}AN7{slash}C2OUT})") (class "Default")
      (node (ref "PIC1") (pin "27") (pinfunction "RE2/~{CS/AN7/C2OUT}_27") (pintype "bidirectional"))
      (node (ref "R105") (pin "1") (pinfunction "A_1") (pintype "passive"))
    )
    (net (code "97") (name "Net-(PIC1-VDDCORE{slash}VCAP)") (class "Default")
      (node (ref "C3") (pin "1") (pinfunction "1_1") (pintype "passive"))
      (node (ref "PIC1") (pin "23") (pinfunction "VDDCORE/VCAP_23") (pintype "bidirectional"))
    )
    (net (code "98") (name "Net-(PIC1-~{MCLR{slash}VPP{slash}RE3})") (class "Default")
      (node (ref "CN_TANIT") (pin "3") (pinfunction "3_3") (pintype "passive"))
      (node (ref "PIC1") (pin "18") (pinfunction "~{MCLR/VPP/RE3}_18") (pintype "input"))
      (node (ref "R1") (pin "1") (pinfunction "A_1") (pintype "passive"))
    )
    (net (code "99") (name "Net-(R29-A)") (class "Default")
      (node (ref "R29") (pin "1") (pinfunction "A_1") (pintype "passive"))
      (node (ref "R53") (pin "2") (pinfunction "E_2") (pintype "passive"))
      (node (ref "R77") (pin "2") (pinfunction "E_2") (pintype "passive"))
      (node (ref "ZOLD_3P1") (pin "2") (pinfunction "1_2") (pintype "passive"))
    )
    (net (code "100") (name "Net-(R29-E)") (class "Default")
      (node (ref "R29") (pin "2") (pinfunction "E_2") (pintype "passive"))
      (node (ref "U$5") (pin "P$5") (pinfunction "S_P$5") (pintype "passive"))
    )
    (net (code "101") (name "Net-(R30-A)") (class "Default")
      (node (ref "R30") (pin "1") (pinfunction "A_1") (pintype "passive"))
      (node (ref "R54") (pin "2") (pinfunction "E_2") (pintype "passive"))
      (node (ref "R78") (pin "2") (pinfunction "E_2") (pintype "passive"))
      (node (ref "ZOLD_3P1") (pin "3") (pinfunction "1_3") (pintype "passive"))
    )
    (net (code "102") (name "Net-(R30-E)") (class "Default")
      (node (ref "R30") (pin "2") (pinfunction "E_2") (pintype "passive"))
      (node (ref "U$5") (pin "P$2") (pinfunction "S_P$2") (pintype "passive"))
    )
    (net (code "103") (name "Net-(R31-A)") (class "Default")
      (node (ref "R31") (pin "1") (pinfunction "A_1") (pintype "passive"))
      (node (ref "R55") (pin "2") (pinfunction "E_2") (pintype "passive"))
      (node (ref "R79") (pin "2") (pinfunction "E_2") (pintype "passive"))
      (node (ref "ZOLD_3P2") (pin "2") (pinfunction "1_2") (pintype "passive"))
    )
    (net (code "104") (name "Net-(R31-E)") (class "Default")
      (node (ref "R31") (pin "2") (pinfunction "E_2") (pintype "passive"))
      (node (ref "U$6") (pin "P$5") (pinfunction "S_P$5") (pintype "passive"))
    )
    (net (code "105") (name "Net-(R32-A)") (class "Default")
      (node (ref "R32") (pin "1") (pinfunction "A_1") (pintype "passive"))
      (node (ref "R56") (pin "2") (pinfunction "E_2") (pintype "passive"))
      (node (ref "R80") (pin "2") (pinfunction "E_2") (pintype "passive"))
      (node (ref "ZOLD_3P2") (pin "3") (pinfunction "1_3") (pintype "passive"))
    )
    (net (code "106") (name "Net-(R32-E)") (class "Default")
      (node (ref "R32") (pin "2") (pinfunction "E_2") (pintype "passive"))
      (node (ref "U$6") (pin "P$2") (pinfunction "S_P$2") (pintype "passive"))
    )
    (net (code "107") (name "Net-(R33-A)") (class "Default")
      (node (ref "R33") (pin "1") (pinfunction "A_1") (pintype "passive"))
      (node (ref "R57") (pin "2") (pinfunction "E_2") (pintype "passive"))
      (node (ref "R81") (pin "2") (pinfunction "E_2") (pintype "passive"))
      (node (ref "ZOLD_3P3") (pin "2") (pinfunction "1_2") (pintype "passive"))
    )
    (net (code "108") (name "Net-(R33-E)") (class "Default")
      (node (ref "R33") (pin "2") (pinfunction "E_2") (pintype "passive"))
      (node (ref "U$7") (pin "P$5") (pinfunction "S_P$5") (pintype "passive"))
    )
    (net (code "109") (name "Net-(R34-A)") (class "Default")
      (node (ref "R34") (pin "1") (pinfunction "A_1") (pintype "passive"))
      (node (ref "R58") (pin "2") (pinfunction "E_2") (pintype "passive"))
      (node (ref "R82") (pin "2") (pinfunction "E_2") (pintype "passive"))
      (node (ref "ZOLD_3P3") (pin "3") (pinfunction "1_3") (pintype "passive"))
    )
    (net (code "110") (name "Net-(R34-E)") (class "Default")
      (node (ref "R34") (pin "2") (pinfunction "E_2") (pintype "passive"))
      (node (ref "U$7") (pin "P$2") (pinfunction "S_P$2") (pintype "passive"))
    )
    (net (code "111") (name "Net-(R35-A)") (class "Default")
      (node (ref "R35") (pin "1") (pinfunction "A_1") (pintype "passive"))
      (node (ref "R59") (pin "2") (pinfunction "E_2") (pintype "passive"))
      (node (ref "R83") (pin "2") (pinfunction "E_2") (pintype "passive"))
      (node (ref "ZOLD_3P4") (pin "2") (pinfunction "1_2") (pintype "passive"))
    )
    (net (code "112") (name "Net-(R35-E)") (class "Default")
      (node (ref "R35") (pin "2") (pinfunction "E_2") (pintype "passive"))
      (node (ref "U$8") (pin "P$5") (pinfunction "S_P$5") (pintype "passive"))
    )
    (net (code "113") (name "Net-(R36-A)") (class "Default")
      (node (ref "R36") (pin "1") (pinfunction "A_1") (pintype "passive"))
      (node (ref "R60") (pin "2") (pinfunction "E_2") (pintype "passive"))
      (node (ref "R84") (pin "2") (pinfunction "E_2") (pintype "passive"))
      (node (ref "ZOLD_3P4") (pin "3") (pinfunction "1_3") (pintype "passive"))
    )
    (net (code "114") (name "Net-(R36-E)") (class "Default")
      (node (ref "R36") (pin "2") (pinfunction "E_2") (pintype "passive"))
      (node (ref "U$8") (pin "P$2") (pinfunction "S_P$2") (pintype "passive"))
    )
    (net (code "115") (name "Net-(R37-A)") (class "Default")
      (node (ref "R37") (pin "1") (pinfunction "A_1") (pintype "passive"))
      (node (ref "R61") (pin "2") (pinfunction "E_2") (pintype "passive"))
      (node (ref "R85") (pin "2") (pinfunction "E_2") (pintype "passive"))
      (node (ref "ZOLD_3P5") (pin "2") (pinfunction "1_2") (pintype "passive"))
    )
    (net (code "116") (name "Net-(R37-E)") (class "Default")
      (node (ref "R37") (pin "2") (pinfunction "E_2") (pintype "passive"))
      (node (ref "U$9") (pin "P$5") (pinfunction "S_P$5") (pintype "passive"))
    )
    (net (code "117") (name "Net-(R38-A)") (class "Default")
      (node (ref "R38") (pin "1") (pinfunction "A_1") (pintype "passive"))
      (node (ref "R62") (pin "2") (pinfunction "E_2") (pintype "passive"))
      (node (ref "R86") (pin "2") (pinfunction "E_2") (pintype "passive"))
      (node (ref "ZOLD_3P5") (pin "3") (pinfunction "1_3") (pintype "passive"))
    )
    (net (code "118") (name "Net-(R38-E)") (class "Default")
      (node (ref "R38") (pin "2") (pinfunction "E_2") (pintype "passive"))
      (node (ref "U$9") (pin "P$2") (pinfunction "S_P$2") (pintype "passive"))
    )
    (net (code "119") (name "Net-(R39-A)") (class "Default")
      (node (ref "R39") (pin "1") (pinfunction "A_1") (pintype "passive"))
      (node (ref "R63") (pin "2") (pinfunction "E_2") (pintype "passive"))
      (node (ref "R87") (pin "2") (pinfunction "E_2") (pintype "passive"))
      (node (ref "ZOLD_3P6") (pin "2") (pinfunction "1_2") (pintype "passive"))
    )
    (net (code "120") (name "Net-(R39-E)") (class "Default")
      (node (ref "R39") (pin "2") (pinfunction "E_2") (pintype "passive"))
      (node (ref "U$10") (pin "P$5") (pinfunction "S_P$5") (pintype "passive"))
    )
    (net (code "121") (name "Net-(R40-A)") (class "Default")
      (node (ref "R40") (pin "1") (pinfunction "A_1") (pintype "passive"))
      (node (ref "R64") (pin "2") (pinfunction "E_2") (pintype "passive"))
      (node (ref "R88") (pin "2") (pinfunction "E_2") (pintype "passive"))
      (node (ref "ZOLD_3P6") (pin "3") (pinfunction "1_3") (pintype "passive"))
    )
    (net (code "122") (name "Net-(R40-E)") (class "Default")
      (node (ref "R40") (pin "2") (pinfunction "E_2") (pintype "passive"))
      (node (ref "U$10") (pin "P$2") (pinfunction "S_P$2") (pintype "passive"))
    )
    (net (code "123") (name "Net-(R41-A)") (class "Default")
      (node (ref "R41") (pin "1") (pinfunction "A_1") (pintype "passive"))
      (node (ref "R65") (pin "2") (pinfunction "E_2") (pintype "passive"))
      (node (ref "R89") (pin "2") (pinfunction "E_2") (pintype "passive"))
      (node (ref "ZOLD_3P7") (pin "2") (pinfunction "1_2") (pintype "passive"))
    )
    (net (code "124") (name "Net-(R41-E)") (class "Default")
      (node (ref "R41") (pin "2") (pinfunction "E_2") (pintype "passive"))
      (node (ref "U$11") (pin "P$5") (pinfunction "S_P$5") (pintype "passive"))
    )
    (net (code "125") (name "Net-(R42-A)") (class "Default")
      (node (ref "R42") (pin "1") (pinfunction "A_1") (pintype "passive"))
      (node (ref "R66") (pin "2") (pinfunction "E_2") (pintype "passive"))
      (node (ref "R90") (pin "2") (pinfunction "E_2") (pintype "passive"))
      (node (ref "ZOLD_3P7") (pin "3") (pinfunction "1_3") (pintype "passive"))
    )
    (net (code "126") (name "Net-(R42-E)") (class "Default")
      (node (ref "R42") (pin "2") (pinfunction "E_2") (pintype "passive"))
      (node (ref "U$11") (pin "P$2") (pinfunction "S_P$2") (pintype "passive"))
    )
    (net (code "127") (name "Net-(R43-A)") (class "Default")
      (node (ref "R43") (pin "1") (pinfunction "A_1") (pintype "passive"))
      (node (ref "R67") (pin "2") (pinfunction "E_2") (pintype "passive"))
      (node (ref "R91") (pin "2") (pinfunction "E_2") (pintype "passive"))
      (node (ref "ZOLD_3P8") (pin "2") (pinfunction "1_2") (pintype "passive"))
    )
    (net (code "128") (name "Net-(R43-E)") (class "Default")
      (node (ref "R43") (pin "2") (pinfunction "E_2") (pintype "passive"))
      (node (ref "U$12") (pin "P$5") (pinfunction "S_P$5") (pintype "passive"))
    )
    (net (code "129") (name "Net-(R44-A)") (class "Default")
      (node (ref "R44") (pin "1") (pinfunction "A_1") (pintype "passive"))
      (node (ref "R68") (pin "2") (pinfunction "E_2") (pintype "passive"))
      (node (ref "R92") (pin "2") (pinfunction "E_2") (pintype "passive"))
      (node (ref "ZOLD_3P8") (pin "3") (pinfunction "1_3") (pintype "passive"))
    )
    (net (code "130") (name "Net-(R44-E)") (class "Default")
      (node (ref "R44") (pin "2") (pinfunction "E_2") (pintype "passive"))
      (node (ref "U$12") (pin "P$2") (pinfunction "S_P$2") (pintype "passive"))
    )
    (net (code "131") (name "Net-(R45-A)") (class "Default")
      (node (ref "R45") (pin "1") (pinfunction "A_1") (pintype "passive"))
      (node (ref "R69") (pin "2") (pinfunction "E_2") (pintype "passive"))
      (node (ref "R93") (pin "2") (pinfunction "E_2") (pintype "passive"))
      (node (ref "ZOLD_3P9") (pin "2") (pinfunction "1_2") (pintype "passive"))
    )
    (net (code "132") (name "Net-(R45-E)") (class "Default")
      (node (ref "R45") (pin "2") (pinfunction "E_2") (pintype "passive"))
      (node (ref "U$13") (pin "P$5") (pinfunction "S_P$5") (pintype "passive"))
    )
    (net (code "133") (name "Net-(R46-A)") (class "Default")
      (node (ref "R46") (pin "1") (pinfunction "A_1") (pintype "passive"))
      (node (ref "R70") (pin "2") (pinfunction "E_2") (pintype "passive"))
      (node (ref "R94") (pin "2") (pinfunction "E_2") (pintype "passive"))
      (node (ref "ZOLD_3P9") (pin "3") (pinfunction "1_3") (pintype "passive"))
    )
    (net (code "134") (name "Net-(R46-E)") (class "Default")
      (node (ref "R46") (pin "2") (pinfunction "E_2") (pintype "passive"))
      (node (ref "U$13") (pin "P$2") (pinfunction "S_P$2") (pintype "passive"))
    )
    (net (code "135") (name "Net-(R47-A)") (class "Default")
      (node (ref "R47") (pin "1") (pinfunction "A_1") (pintype "passive"))
      (node (ref "R71") (pin "2") (pinfunction "E_2") (pintype "passive"))
      (node (ref "R95") (pin "2") (pinfunction "E_2") (pintype "passive"))
      (node (ref "ZOLD_3P10") (pin "2") (pinfunction "1_2") (pintype "passive"))
    )
    (net (code "136") (name "Net-(R47-E)") (class "Default")
      (node (ref "R47") (pin "2") (pinfunction "E_2") (pintype "passive"))
      (node (ref "U$14") (pin "P$5") (pinfunction "S_P$5") (pintype "passive"))
    )
    (net (code "137") (name "Net-(R48-A)") (class "Default")
      (node (ref "R48") (pin "1") (pinfunction "A_1") (pintype "passive"))
      (node (ref "R72") (pin "2") (pinfunction "E_2") (pintype "passive"))
      (node (ref "R96") (pin "2") (pinfunction "E_2") (pintype "passive"))
      (node (ref "ZOLD_3P10") (pin "3") (pinfunction "1_3") (pintype "passive"))
    )
    (net (code "138") (name "Net-(R48-E)") (class "Default")
      (node (ref "R48") (pin "2") (pinfunction "E_2") (pintype "passive"))
      (node (ref "U$14") (pin "P$2") (pinfunction "S_P$2") (pintype "passive"))
    )
    (net (code "139") (name "Net-(R49-A)") (class "Default")
      (node (ref "R49") (pin "1") (pinfunction "A_1") (pintype "passive"))
      (node (ref "R73") (pin "2") (pinfunction "E_2") (pintype "passive"))
      (node (ref "R97") (pin "2") (pinfunction "E_2") (pintype "passive"))
      (node (ref "ZOLD_3P11") (pin "2") (pinfunction "1_2") (pintype "passive"))
    )
    (net (code "140") (name "Net-(R49-E)") (class "Default")
      (node (ref "R49") (pin "2") (pinfunction "E_2") (pintype "passive"))
      (node (ref "U$15") (pin "P$5") (pinfunction "S_P$5") (pintype "passive"))
    )
    (net (code "141") (name "Net-(R50-A)") (class "Default")
      (node (ref "R50") (pin "1") (pinfunction "A_1") (pintype "passive"))
      (node (ref "R74") (pin "2") (pinfunction "E_2") (pintype "passive"))
      (node (ref "R98") (pin "2") (pinfunction "E_2") (pintype "passive"))
      (node (ref "ZOLD_3P11") (pin "3") (pinfunction "1_3") (pintype "passive"))
    )
    (net (code "142") (name "Net-(R50-E)") (class "Default")
      (node (ref "R50") (pin "2") (pinfunction "E_2") (pintype "passive"))
      (node (ref "U$15") (pin "P$2") (pinfunction "S_P$2") (pintype "passive"))
    )
    (net (code "143") (name "Net-(R51-A)") (class "Default")
      (node (ref "R51") (pin "1") (pinfunction "A_1") (pintype "passive"))
      (node (ref "R75") (pin "2") (pinfunction "E_2") (pintype "passive"))
      (node (ref "R99") (pin "2") (pinfunction "E_2") (pintype "passive"))
      (node (ref "ZOLD_3P12") (pin "2") (pinfunction "1_2") (pintype "passive"))
    )
    (net (code "144") (name "Net-(R51-E)") (class "Default")
      (node (ref "R51") (pin "2") (pinfunction "E_2") (pintype "passive"))
      (node (ref "U$16") (pin "P$5") (pinfunction "S_P$5") (pintype "passive"))
    )
    (net (code "145") (name "Net-(R52-E)") (class "Default")
      (node (ref "R52") (pin "2") (pinfunction "E_2") (pintype "passive"))
      (node (ref "U$16") (pin "P$2") (pinfunction "S_P$2") (pintype "passive"))
    )
    (net (code "146") (name "Net-(R100-E)") (class "Default")
      (node (ref "R100") (pin "2") (pinfunction "E_2") (pintype "passive"))
      (node (ref "R52") (pin "1") (pinfunction "A_1") (pintype "passive"))
      (node (ref "R76") (pin "2") (pinfunction "E_2") (pintype "passive"))
      (node (ref "ZOLD_3P12") (pin "3") (pinfunction "1_3") (pintype "passive"))
    )
    (net (code "147") (name "Net-(R125-E)") (class "Default")
      (node (ref "CN_CANLEZAR") (pin "1") (pinfunction "1_1") (pintype "passive"))
      (node (ref "R125") (pin "2") (pinfunction "E_2") (pintype "passive"))
    )
    (net (code "148") (name "Net-(R126-A)") (class "Default")
      (node (ref "CN_CANLEZAR") (pin "3") (pinfunction "3_3") (pintype "passive"))
      (node (ref "R126") (pin "1") (pinfunction "A_1") (pintype "passive"))
    )
    (net (code "149") (name "unconnected-(CANIC-VREF-Pad5)") (class "Default")
      (node (ref "CANIC") (pin "5") (pinfunction "VREF_5") (pintype "output"))
    )
    (net (code "150") (name "unconnected-(CN_RJ1-Pad1)") (class "Default")
      (node (ref "CN_RJ1") (pin "1") (pinfunction "1_1") (pintype "passive"))
    )
    (net (code "151") (name "unconnected-(CN_RJ1-Pad2)") (class "Default")
      (node (ref "CN_RJ1") (pin "2") (pinfunction "2_2") (pintype "passive"))
    )
    (net (code "152") (name "unconnected-(CN_RJ1-Pad3)") (class "Default")
      (node (ref "CN_RJ1") (pin "3") (pinfunction "3_3") (pintype "passive"))
    )
    (net (code "153") (name "unconnected-(CN_RJ1-Pad6)") (class "Default")
      (node (ref "CN_RJ1") (pin "6") (pinfunction "6_6") (pintype "passive"))
    )
    (net (code "154") (name "unconnected-(CN_RJ2-Pad1)") (class "Default")
      (node (ref "CN_RJ2") (pin "1") (pinfunction "1_1") (pintype "passive"))
    )
    (net (code "155") (name "unconnected-(CN_RJ2-Pad2)") (class "Default")
      (node (ref "CN_RJ2") (pin "2") (pinfunction "2_2") (pintype "passive"))
    )
    (net (code "156") (name "unconnected-(CN_RJ2-Pad3)") (class "Default")
      (node (ref "CN_RJ2") (pin "3") (pinfunction "3_3") (pintype "passive"))
    )
    (net (code "157") (name "unconnected-(CN_RJ2-Pad6)") (class "Default")
      (node (ref "CN_RJ2") (pin "6") (pinfunction "6_6") (pintype "passive"))
    )
    (net (code "158") (name "unconnected-(IC9-14_SDO-Pad14)") (class "Default")
      (node (ref "IC9") (pin "14") (pinfunction "14_SDO_14") (pintype "output"))
    )
    (net (code "159") (name "unconnected-(PIC1-NC-Pad34)") (class "Default")
      (node (ref "PIC1") (pin "34") (pinfunction "NC_34") (pintype "no_connect"))
    )
    (net (code "160") (name "unconnected-(PIC1-NC_2-Pad12)") (class "Default")
      (node (ref "PIC1") (pin "12") (pinfunction "NC_2_12") (pintype "no_connect"))
    )
    (net (code "161") (name "unconnected-(PIC1-NC_3-Pad13)") (class "Default")
      (node (ref "PIC1") (pin "13") (pinfunction "NC_3_13") (pintype "no_connect"))
    )
    (net (code "162") (name "unconnected-(PIC1-NC_4-Pad33)") (class "Default")
      (node (ref "PIC1") (pin "33") (pinfunction "NC_4_33") (pintype "no_connect"))
    )
    (net (code "163") (name "unconnected-(PIC1-RE0{slash}~{RD{slash}AN5}-Pad25)") (class "Default")
      (node (ref "PIC1") (pin "25") (pinfunction "RE0/~{RD/AN5}_25") (pintype "bidirectional"))
    )
    (net (code "164") (name "unconnected-(U$20-PadP$2)") (class "Default")
      (node (ref "U$20") (pin "P$2") (pinfunction "P$2_P$2") (pintype "bidirectional"))
    )
  )
)
